# 1013-B-solarwhat-power.net
KiCad netlist of a schematic drawn in EAGLE
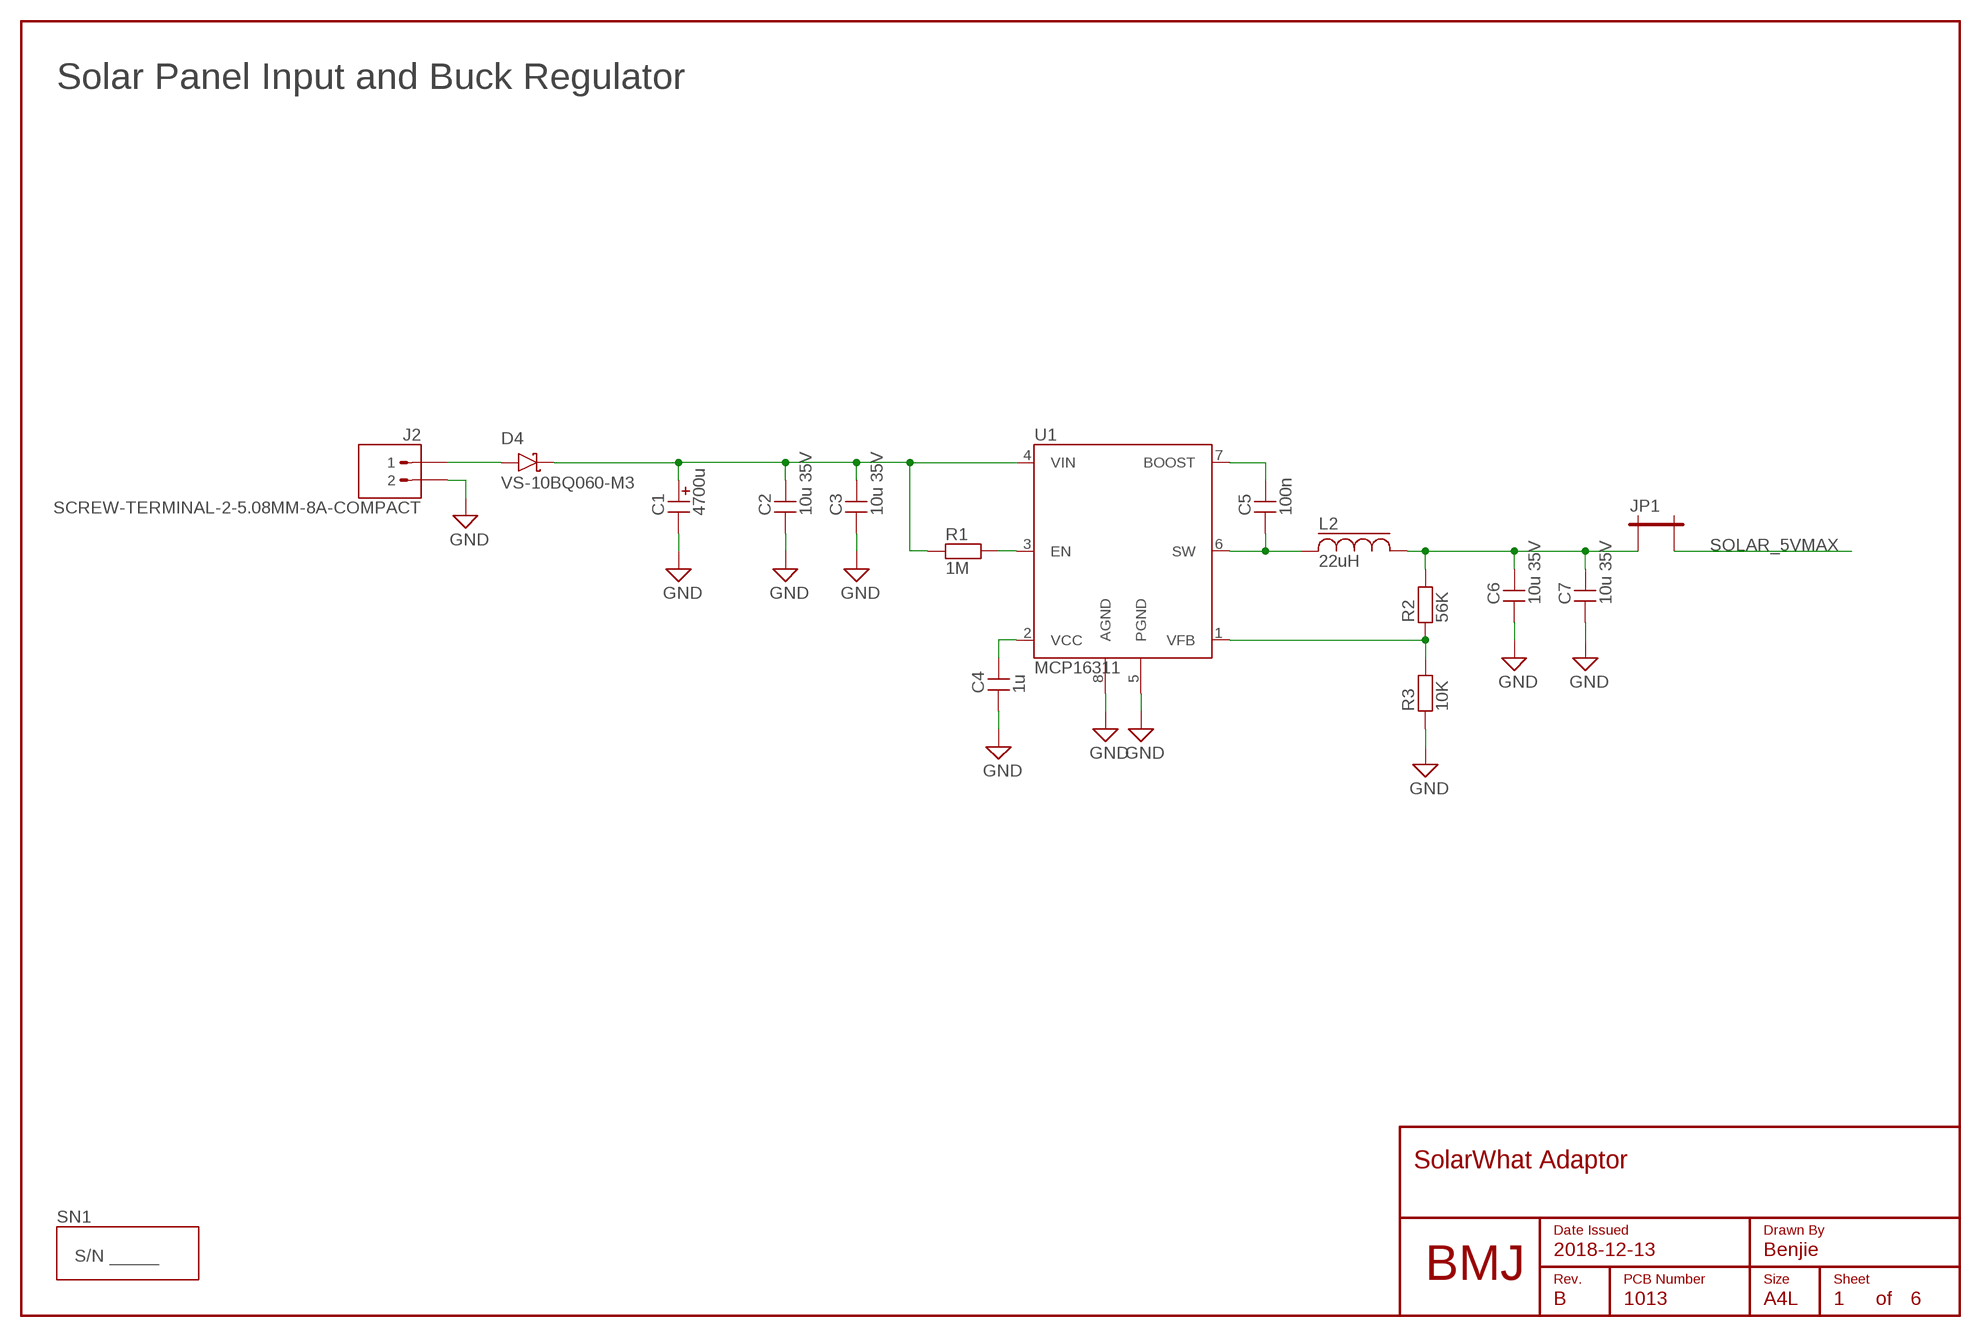
[diagram p0: schematic, sheet 1]
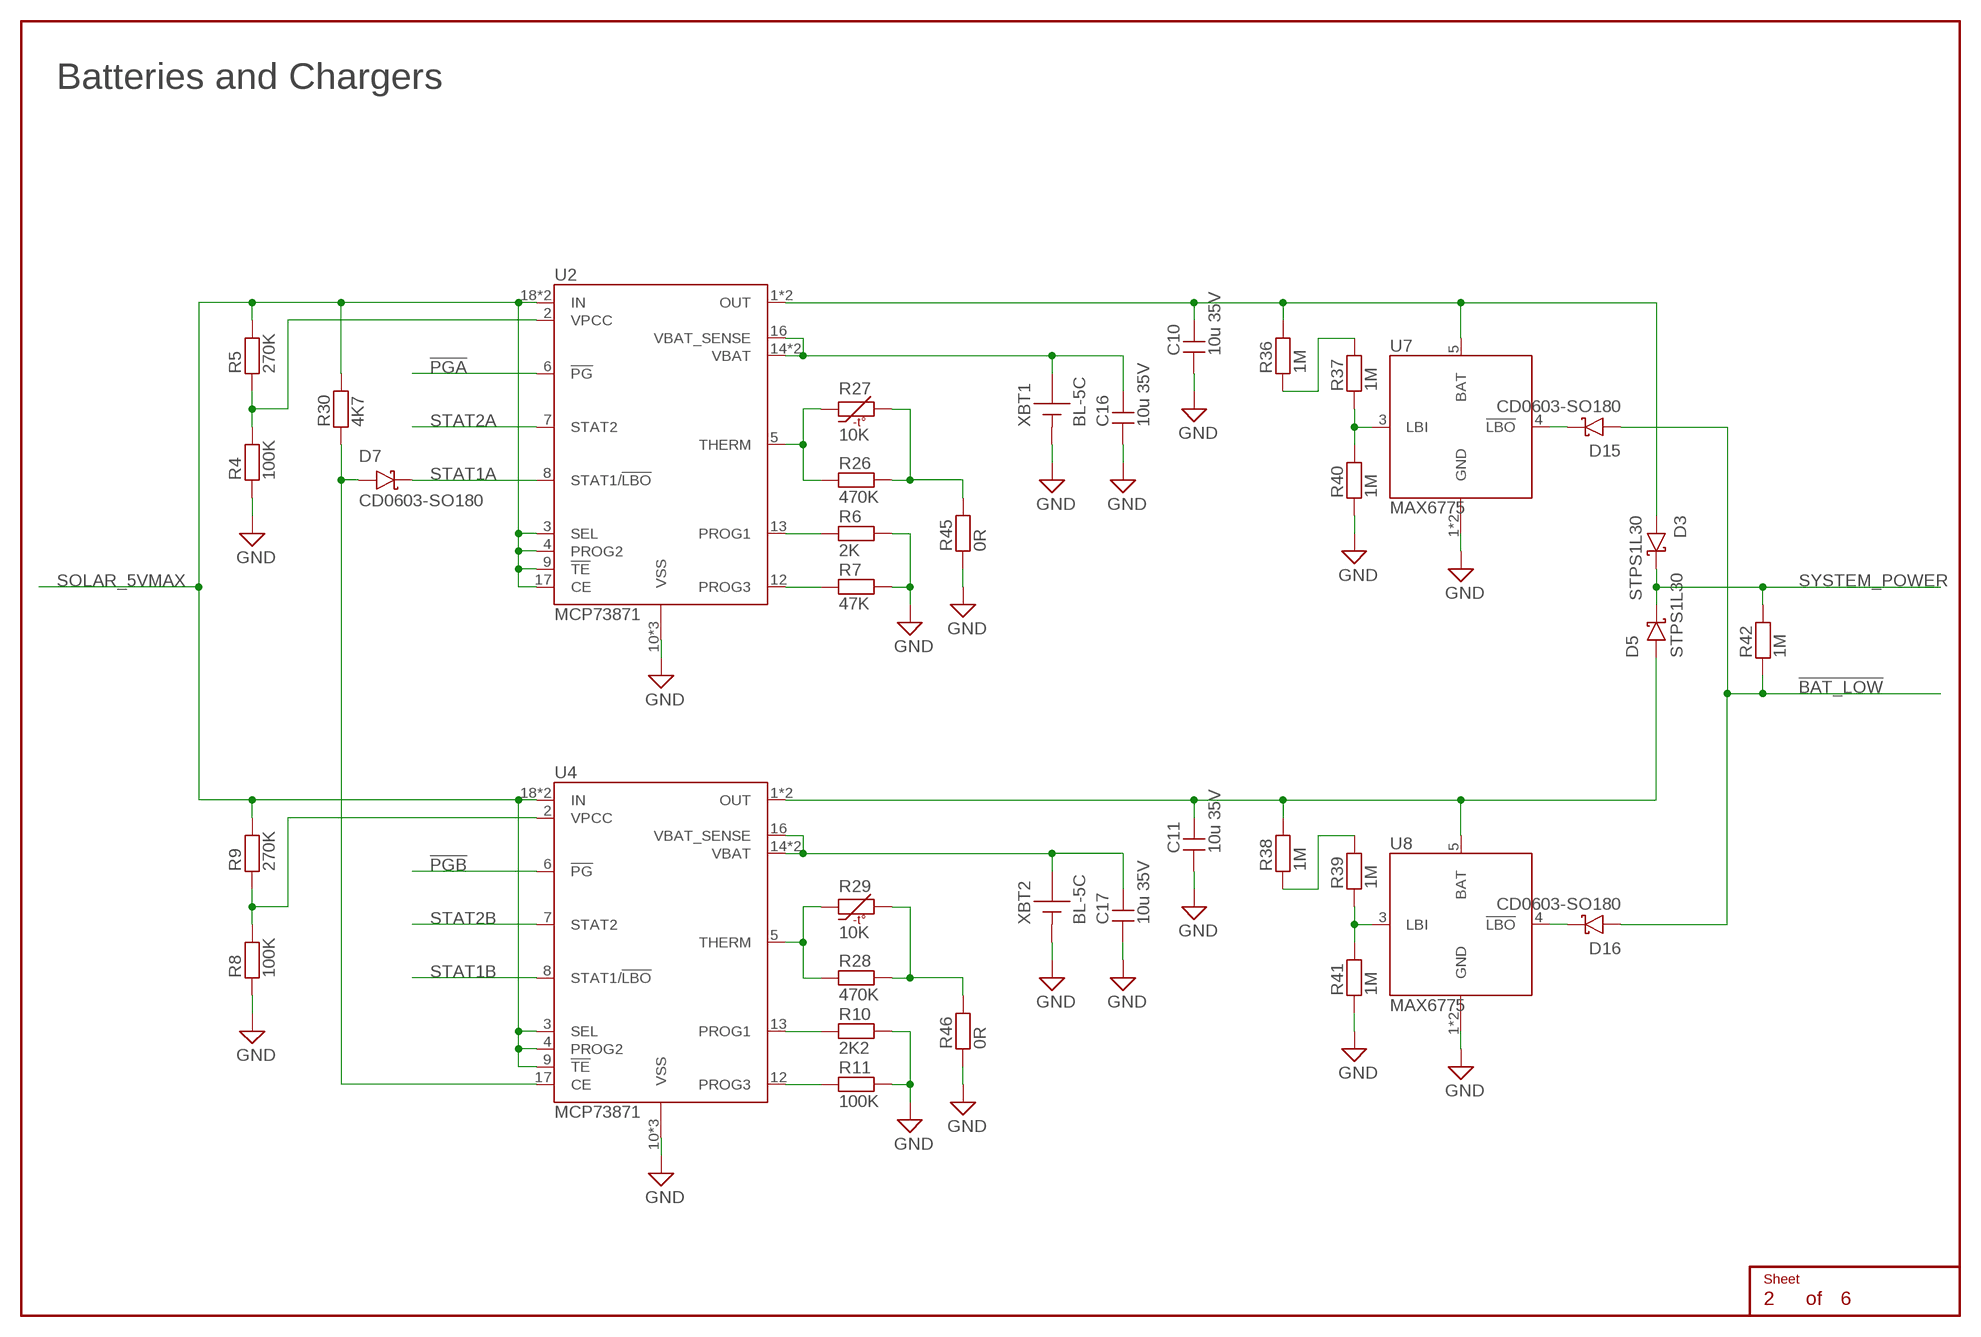
[diagram p1: schematic, sheet 2]
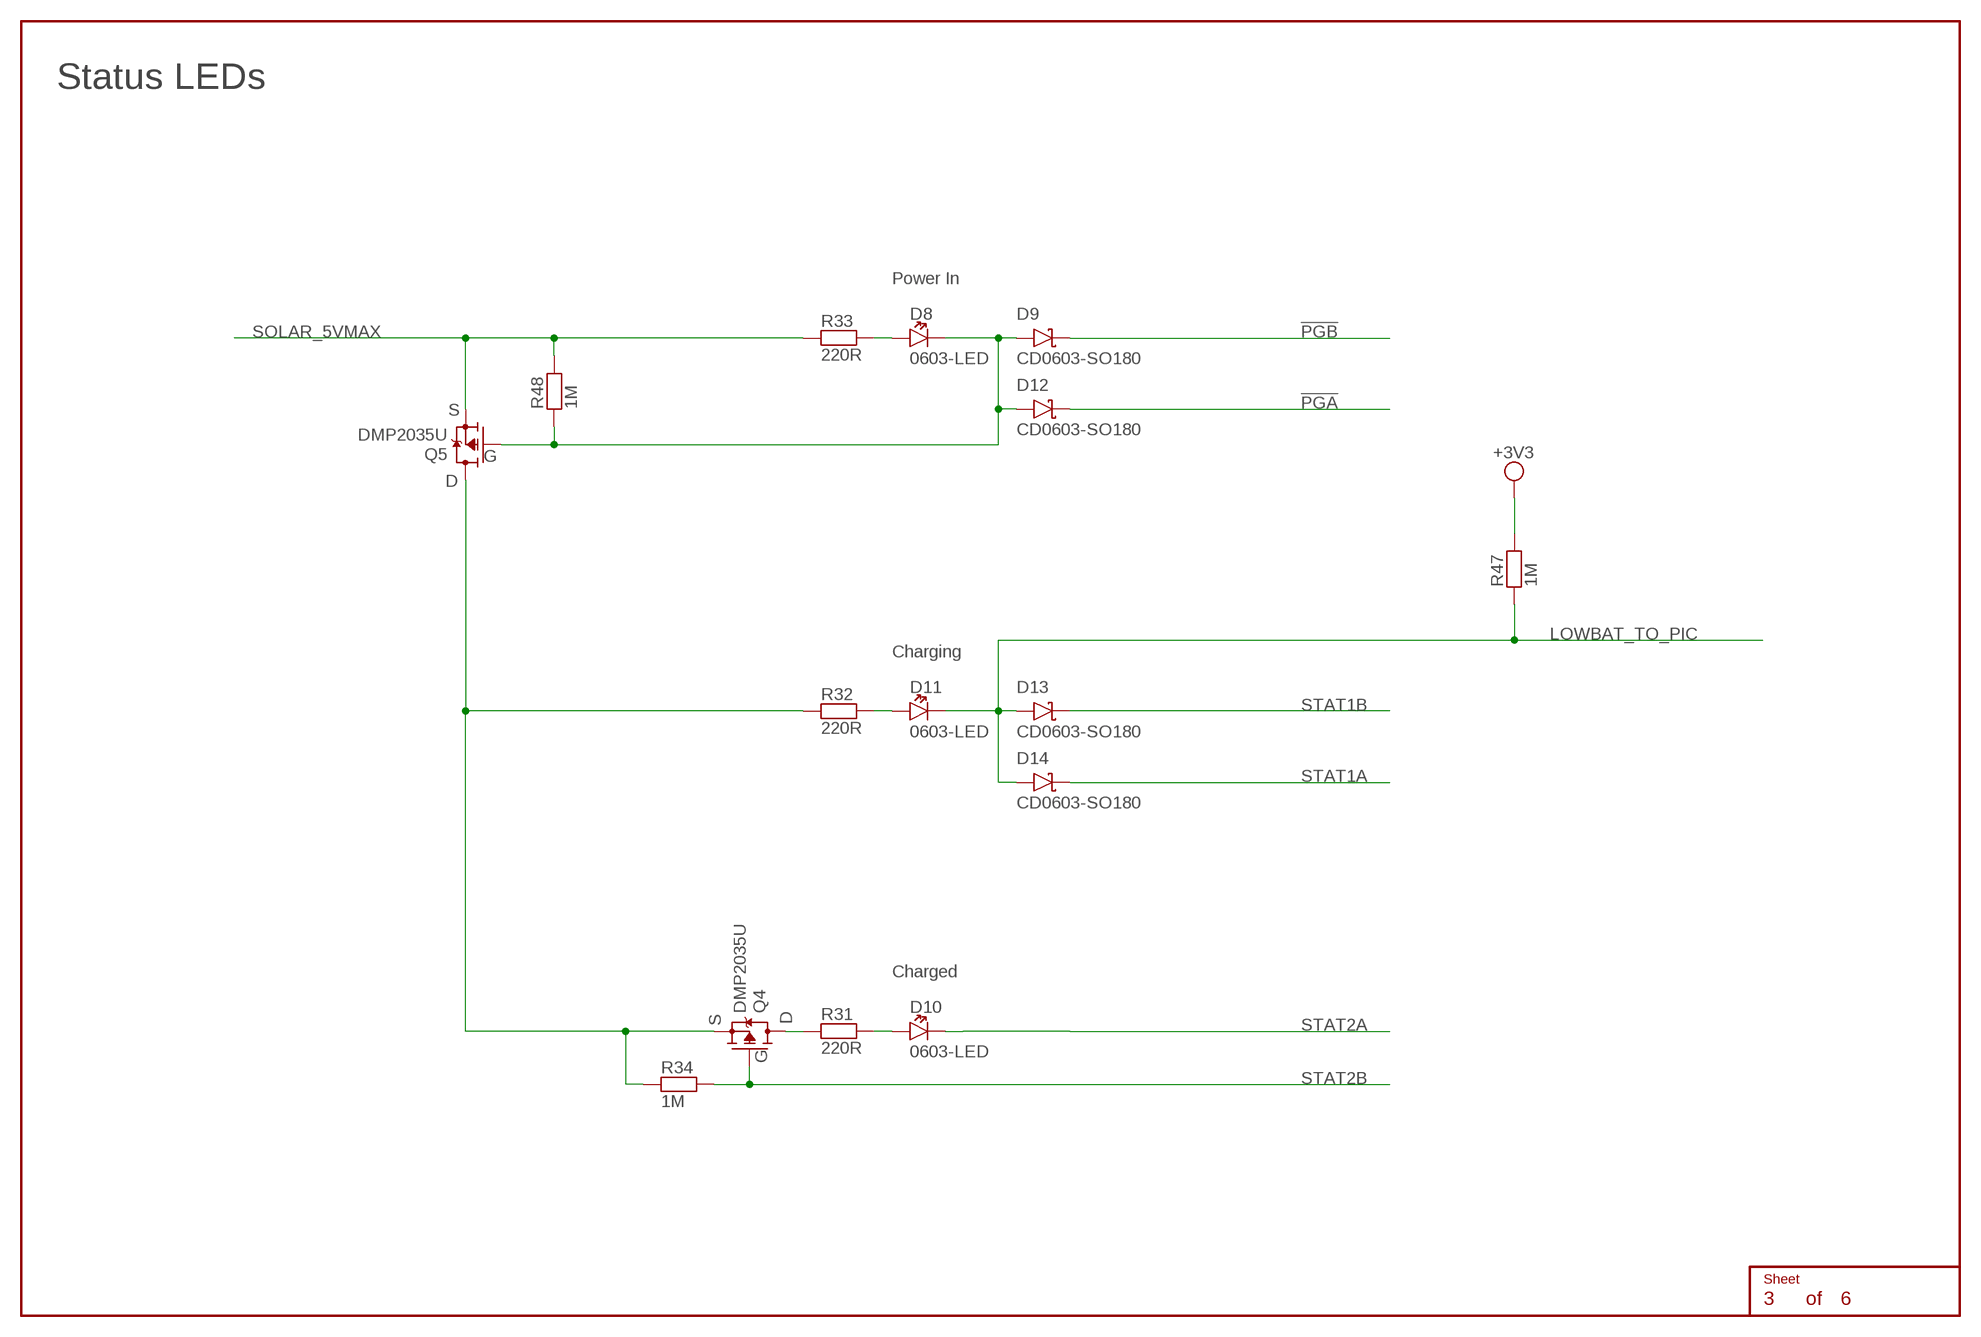
[diagram p2: schematic, sheet 3]
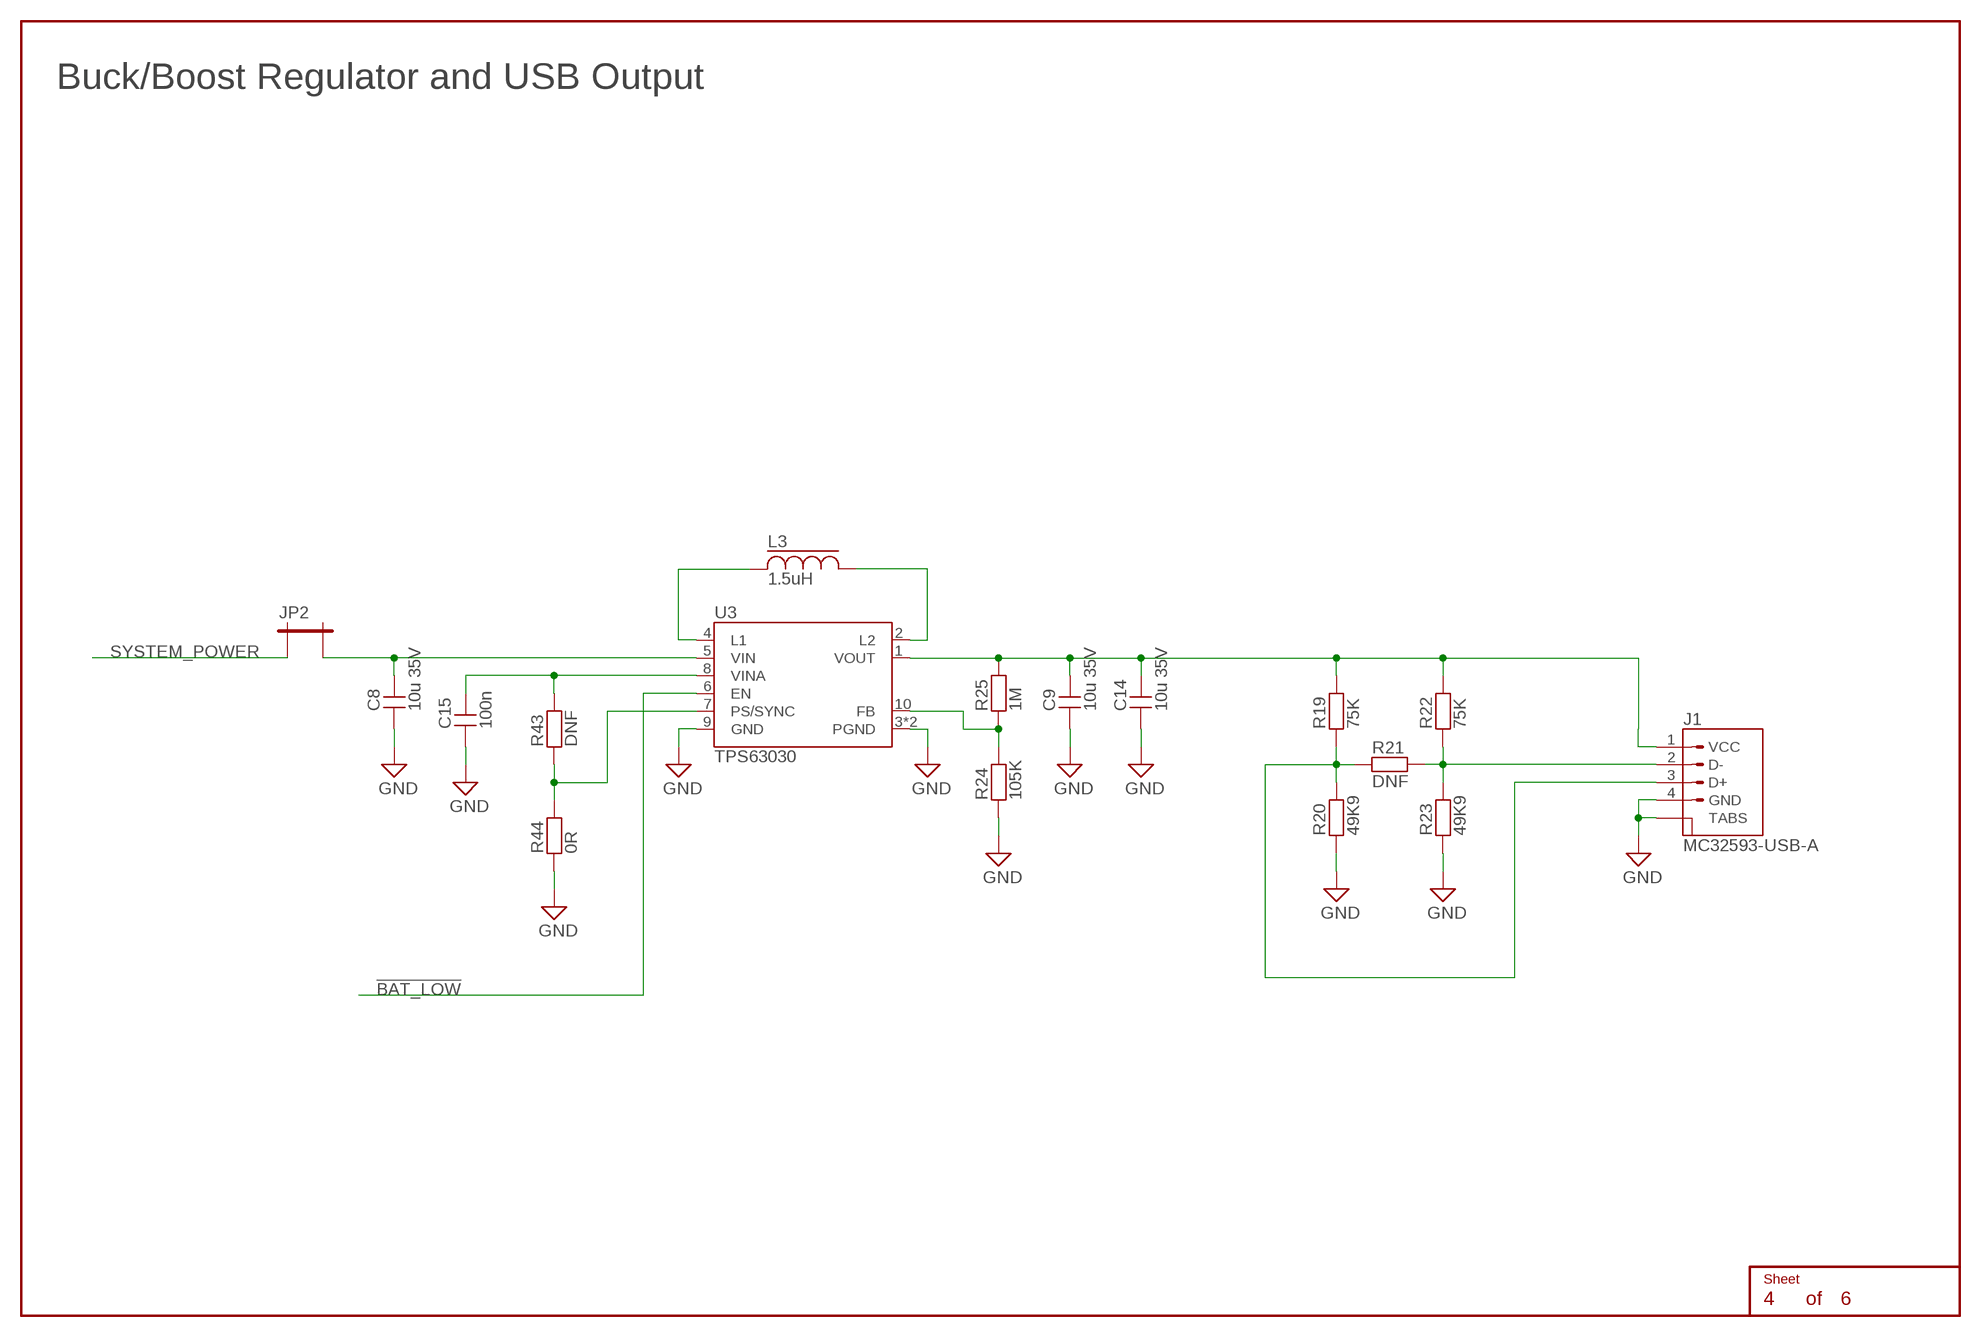
[diagram p3: schematic, sheet 4]
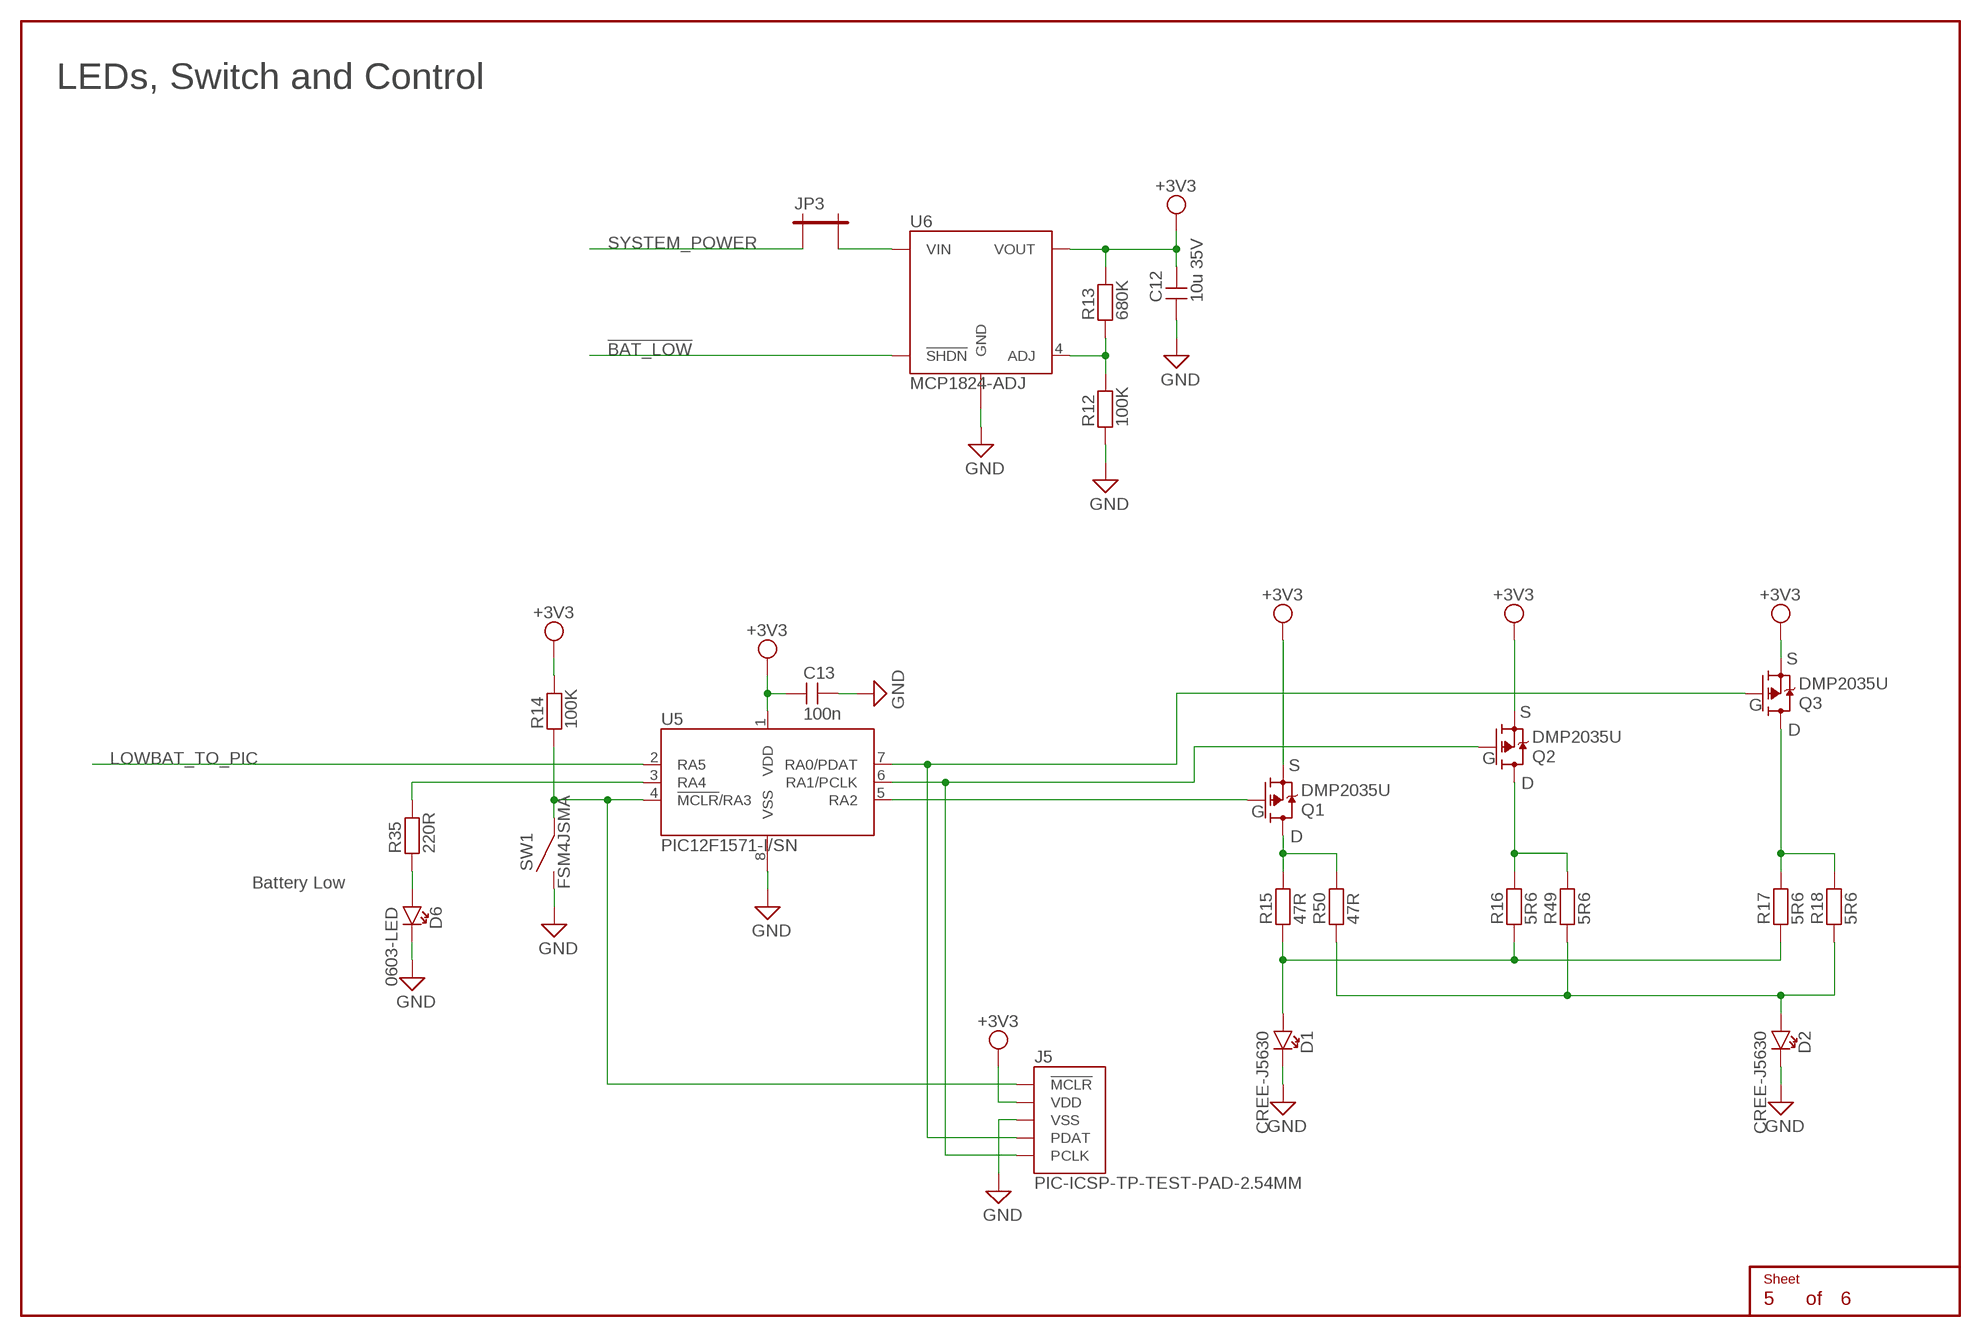
[diagram p4: schematic, sheet 5]
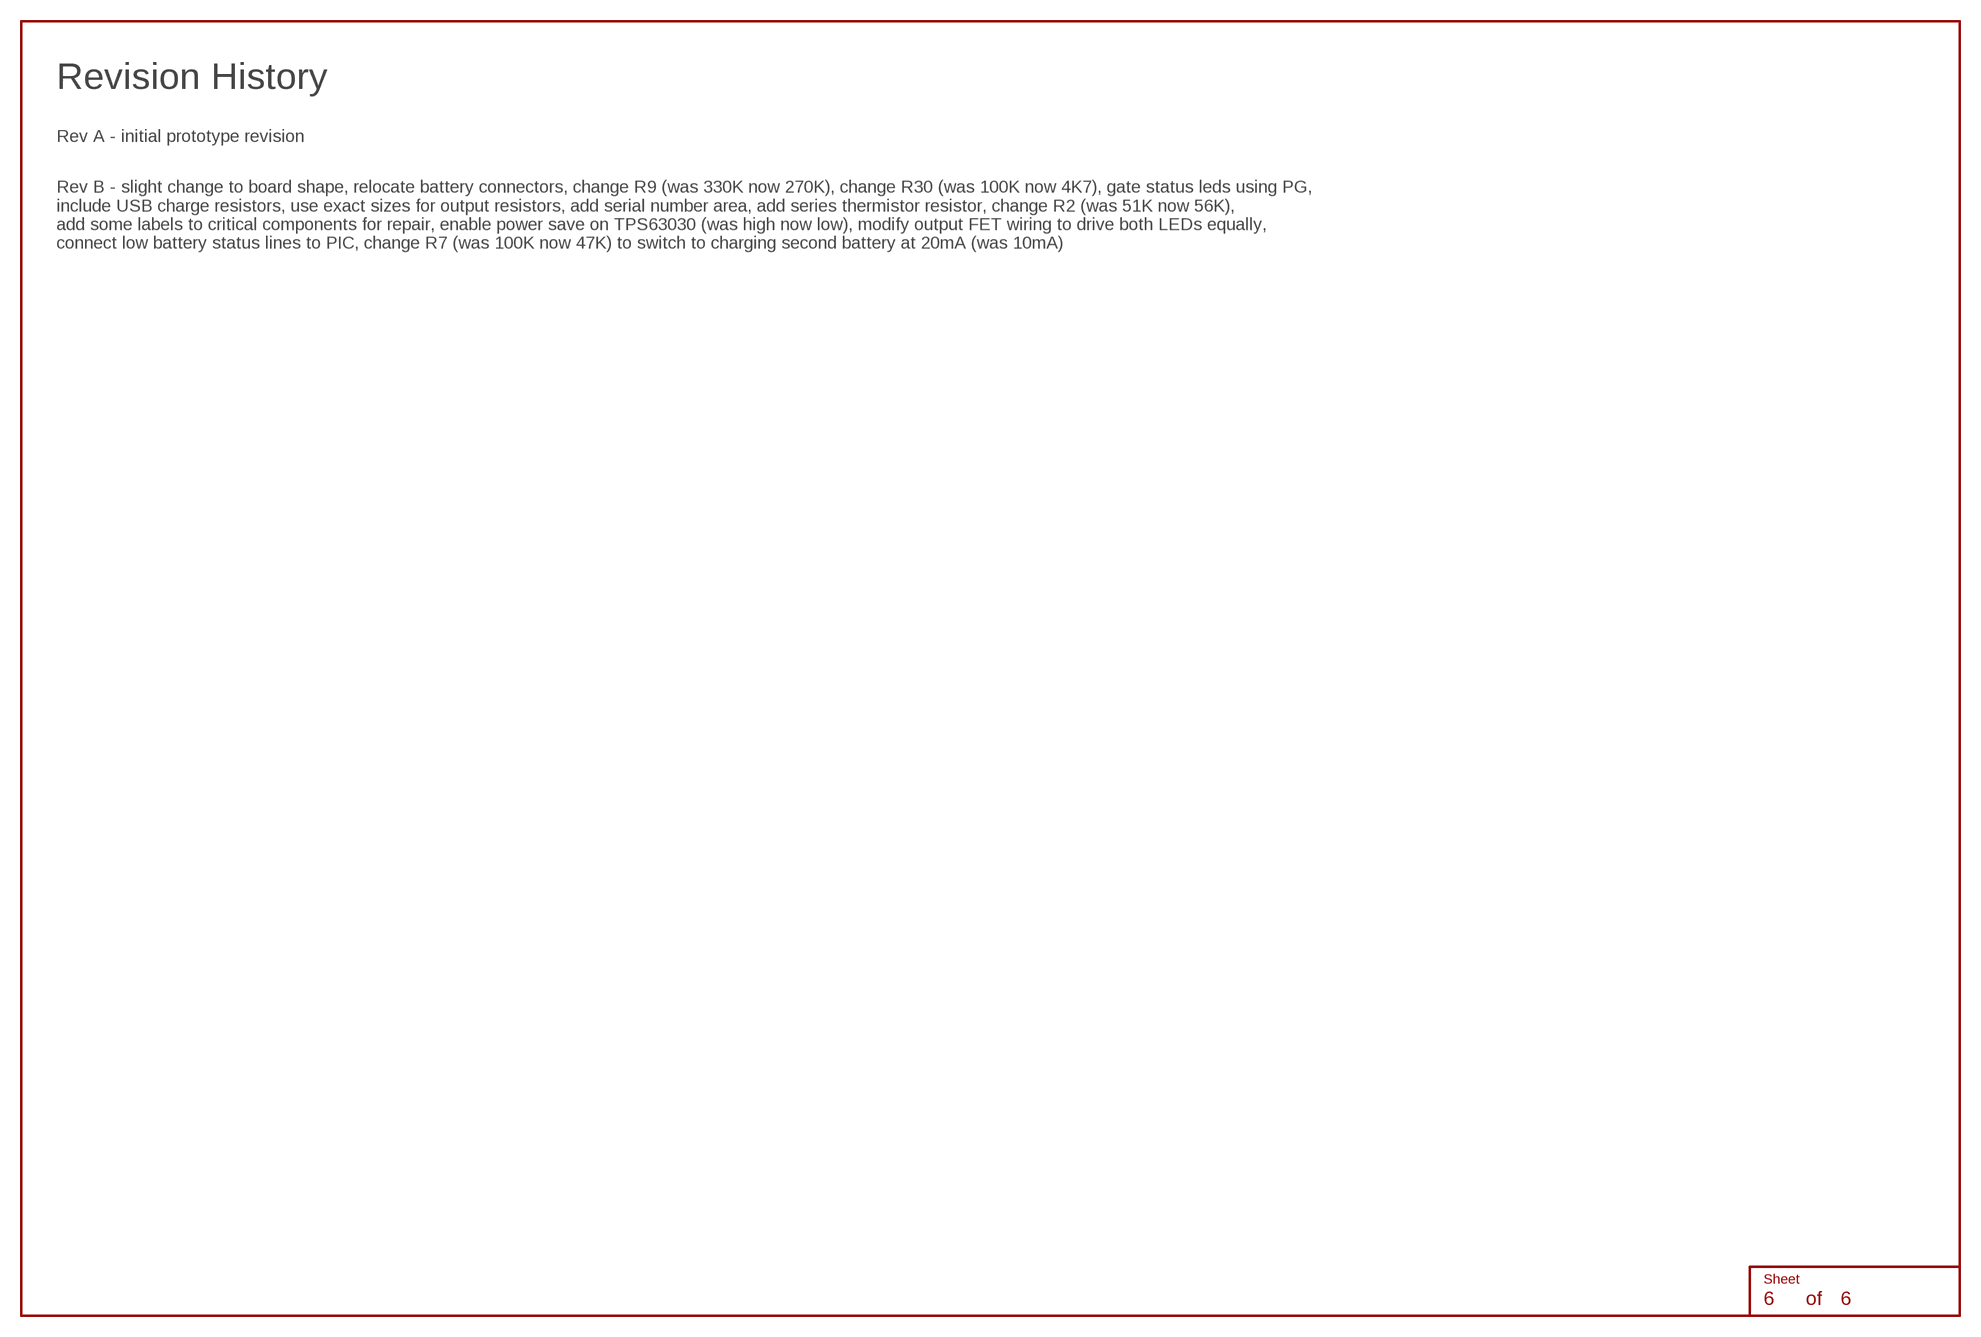
[diagram p5: schematic, sheet 6]

(export (version "E")
  (design (tool "Eeschema 10.0.6"))
  (components
    (comp (ref "C12")
      (value "10u 35V")
      (footprint "eagle-import:1206")
      (fields (field (name "MPN") "1206 10uF 35V 10% X7R"))
      (libsource (lib "eagle-import") (part "1206-10U-35V"))
    )
    (comp (ref "C13")
      (value "100n")
      (footprint "eagle-import:0603")
      (fields (field (name "MPN") "0603 100nF 50V 10% X7R"))
      (libsource (lib "eagle-import") (part "0603-100N"))
    )
    (comp (ref "D1")
      (value "CREE-J5630")
      (footprint "eagle-import:CREE-J5630")
      (libsource (lib "eagle-import") (part "CREE-J5630"))
    )
    (comp (ref "D2")
      (value "CREE-J5630")
      (footprint "eagle-import:CREE-J5630")
      (libsource (lib "eagle-import") (part "CREE-J5630"))
    )
    (comp (ref "D6")
      (value "0603-LED")
      (footprint "eagle-import:0603-LED")
      (fields (field (name "MPN") "TruOpto OSR50603C1E"))
      (libsource (lib "eagle-import") (part "0603-LED"))
    )
    (comp (ref "FRAME4")
      (value "A4L-CONTINUATION")
      (footprint "eagle-import:EMPTY")
      (libsource (lib "eagle-import") (part "A4L-CONTINUATION"))
    )
    (comp (ref "J5")
      (value "PIC-ICSP-TP-TEST-PAD-2.54MM")
      (footprint "eagle-import:PIC-ICSP-TEST-PAD-2.54MM")
      (libsource (lib "eagle-import") (part "PIC-ICSP-TP-TEST-PAD-2.54MM"))
    )
    (comp (ref "JP3")
      (value "SOLDER-JUMPER-2MM")
      (footprint "eagle-import:SOLDER-JUMPER-2MM")
      (libsource (lib "eagle-import") (part "SOLDER-JUMPER-2MM"))
    )
    (comp (ref "Q1")
      (value "DMP2035U")
      (footprint "eagle-import:SOT-23")
      (fields (field (name "MPN") "Diodes Inc DMP2035U"))
      (libsource (lib "eagle-import") (part "DMP2035U"))
    )
    (comp (ref "Q2")
      (value "DMP2035U")
      (footprint "eagle-import:SOT-23")
      (fields (field (name "MPN") "Diodes Inc DMP2035U"))
      (libsource (lib "eagle-import") (part "DMP2035U"))
    )
    (comp (ref "Q3")
      (value "DMP2035U")
      (footprint "eagle-import:SOT-23")
      (fields (field (name "MPN") "Diodes Inc DMP2035U"))
      (libsource (lib "eagle-import") (part "DMP2035U"))
    )
    (comp (ref "R12")
      (value "100K")
      (footprint "eagle-import:0603")
      (fields (field (name "MPN") "0603 100K 1% 100mW"))
      (libsource (lib "eagle-import") (part "0603-1%-100K"))
    )
    (comp (ref "R13")
      (value "680K")
      (footprint "eagle-import:0603")
      (fields (field (name "MPN") "0603 680K 1% 100mW"))
      (libsource (lib "eagle-import") (part "0603-1%-680K"))
    )
    (comp (ref "R14")
      (value "100K")
      (footprint "eagle-import:0603")
      (fields (field (name "MPN") "0603 100K 1% 100mW"))
      (libsource (lib "eagle-import") (part "0603-1%-100K"))
    )
    (comp (ref "R15")
      (value "47R")
      (footprint "eagle-import:0603")
      (fields (field (name "MPN") "0603 47R 1% 100mW"))
      (libsource (lib "eagle-import") (part "0603-1%-47R"))
    )
    (comp (ref "R16")
      (value "5R6")
      (footprint "eagle-import:0805")
      (libsource (lib "eagle-import") (part "0805"))
    )
    (comp (ref "R17")
      (value "5R6")
      (footprint "eagle-import:0805")
      (libsource (lib "eagle-import") (part "0805"))
    )
    (comp (ref "R18")
      (value "5R6")
      (footprint "eagle-import:0805")
      (libsource (lib "eagle-import") (part "0805"))
    )
    (comp (ref "R35")
      (value "220R")
      (footprint "eagle-import:0603")
      (fields (field (name "MPN") "0603 220R 1% 100mW"))
      (libsource (lib "eagle-import") (part "0603-1%-220R"))
    )
    (comp (ref "R49")
      (value "5R6")
      (footprint "eagle-import:0805")
      (libsource (lib "eagle-import") (part "0805"))
    )
    (comp (ref "R50")
      (value "47R")
      (footprint "eagle-import:0603")
      (fields (field (name "MPN") "0603 47R 1% 100mW"))
      (libsource (lib "eagle-import") (part "0603-1%-47R"))
    )
    (comp (ref "SW1")
      (value "FSM4JSMA")
      (footprint "eagle-import:ALCOSWITCH-FSM4JSMA")
      (fields (field (name "MPN") "Alcoswitch FSM4JSMA"))
      (libsource (lib "eagle-import") (part "FSM4JSMA"))
    )
    (comp (ref "U5")
      (value "PIC12F1571-I/SN")
      (footprint "eagle-import:SOIC-8")
      (fields (field (name "MPN") "Microchip PIC12F1571-I/SN"))
      (libsource (lib "eagle-import") (part "PIC12F1571-I/SN"))
    )
    (comp (ref "U6")
      (value "MCP1824-ADJ")
      (footprint "eagle-import:SOT-23-5")
      (libsource (lib "eagle-import") (part "MCP1824-ADJ"))
    )
    (comp (ref "C1")
      (value "4700u")
      (footprint "eagle-import:18X36-TH-FLAT")
      (fields (field (name "MPN") "Panasonic ECA1VAM472X"))
      (libsource (lib "eagle-import") (part "BIG-ELECTROLYTIC"))
    )
    (comp (ref "C2")
      (value "10u 35V")
      (footprint "eagle-import:1206")
      (fields (field (name "MPN") "1206 10uF 35V 10% X7R"))
      (libsource (lib "eagle-import") (part "1206-10U-35V"))
    )
    (comp (ref "C3")
      (value "10u 35V")
      (footprint "eagle-import:1206")
      (fields (field (name "MPN") "1206 10uF 35V 10% X7R"))
      (libsource (lib "eagle-import") (part "1206-10U-35V"))
    )
    (comp (ref "C4")
      (value "1u")
      (footprint "eagle-import:0805")
      (fields (field (name "MPN") "0805 1uF 50V 10% X7R"))
      (libsource (lib "eagle-import") (part "0805-1U"))
    )
    (comp (ref "C5")
      (value "100n")
      (footprint "eagle-import:0603")
      (fields (field (name "MPN") "0603 100nF 50V 10% X7R"))
      (libsource (lib "eagle-import") (part "0603-100N"))
    )
    (comp (ref "C6")
      (value "10u 35V")
      (footprint "eagle-import:1206")
      (fields (field (name "MPN") "1206 10uF 35V 10% X7R"))
      (libsource (lib "eagle-import") (part "1206-10U-35V"))
    )
    (comp (ref "C7")
      (value "10u 35V")
      (footprint "eagle-import:1206")
      (fields (field (name "MPN") "1206 10uF 35V 10% X7R"))
      (libsource (lib "eagle-import") (part "1206-10U-35V"))
    )
    (comp (ref "D4")
      (value "VS-10BQ060-M3")
      (footprint "eagle-import:SMB-ST")
      (fields (field (name "MPN") "Vishay VS-10BQ060-M3"))
      (libsource (lib "eagle-import") (part "VS-10BQ060-M3"))
    )
    (comp (ref "FRAME1")
      (value "A4L-NEW")
      (footprint "eagle-import:PCB-ID")
      (fields
        (field (name "DATEISSUED") "2018-12-13")
        (field (name "PCBNUMBER") "1013")
        (field (name "REVISION") "B")
        (field (name "TITLE") "SolarWhat Adaptor")
        (field (name "DRAWNBY") "Benjie")
      )
      (libsource (lib "eagle-import") (part "A4L-NEW"))
    )
    (comp (ref "J2")
      (value "SCREW-TERMINAL-2-5.08MM-8A-COMPACT")
      (footprint "eagle-import:CTBP0508_2")
      (fields (field (name "MPN") "CamdenBoss CTBP0508/2"))
      (libsource (lib "eagle-import") (part "SCREW-TERMINAL-2-5.08MM-8A-COMPACT"))
    )
    (comp (ref "JP1")
      (value "SOLDER-JUMPER-2MM")
      (footprint "eagle-import:SOLDER-JUMPER-2MM")
      (libsource (lib "eagle-import") (part "SOLDER-JUMPER-2MM"))
    )
    (comp (ref "L2")
      (value "22uH")
      (footprint "eagle-import:TDK-VLSX6045EX")
      (fields (field (name "MPN") "VLS6045EX-220M"))
      (libsource (lib "eagle-import") (part "TDK-VLSX6045EX-220M"))
    )
    (comp (ref "LOGO1")
      (value "BMJ-LOGO")
      (footprint "eagle-import:BMJ-LOGO")
      (libsource (lib "eagle-import") (part "BMJ-LOGO"))
    )
    (comp (ref "R1")
      (value "1M")
      (footprint "eagle-import:0603")
      (fields (field (name "MPN") "0603 1M 1% 100mW"))
      (libsource (lib "eagle-import") (part "0603-1%-1M"))
    )
    (comp (ref "R2")
      (value "56K")
      (footprint "eagle-import:0603")
      (libsource (lib "eagle-import") (part "0603-1%-56K"))
    )
    (comp (ref "R3")
      (value "10K")
      (footprint "eagle-import:0603")
      (fields (field (name "MPN") "0603 10K 1% 100mW"))
      (libsource (lib "eagle-import") (part "0603-1%-10K"))
    )
    (comp (ref "SN1")
      (value "SERIAL-NUMBER-AREA")
      (footprint "eagle-import:SERIAL-NUMBER-AREA-SMALL")
      (libsource (lib "eagle-import") (part "SERIAL-NUMBER-AREA"))
    )
    (comp (ref "U1")
      (value "MCP16311")
      (footprint "eagle-import:MSOP-8")
      (fields (field (name "MPN") "Microchip MCP16311T-E/MS"))
      (libsource (lib "eagle-import") (part "MCP16311"))
    )
    (comp (ref "C8")
      (value "10u 35V")
      (footprint "eagle-import:1206")
      (fields (field (name "MPN") "1206 10uF 35V 10% X7R"))
      (libsource (lib "eagle-import") (part "1206-10U-35V"))
    )
    (comp (ref "C9")
      (value "10u 35V")
      (footprint "eagle-import:1206")
      (fields (field (name "MPN") "1206 10uF 35V 10% X7R"))
      (libsource (lib "eagle-import") (part "1206-10U-35V"))
    )
    (comp (ref "C14")
      (value "10u 35V")
      (footprint "eagle-import:1206")
      (fields (field (name "MPN") "1206 10uF 35V 10% X7R"))
      (libsource (lib "eagle-import") (part "1206-10U-35V"))
    )
    (comp (ref "C15")
      (value "100n")
      (footprint "eagle-import:0603")
      (fields (field (name "MPN") "0603 100nF 50V 10% X7R"))
      (libsource (lib "eagle-import") (part "0603-100N"))
    )
    (comp (ref "FRAME3")
      (value "A4L-CONTINUATION")
      (footprint "eagle-import:EMPTY")
      (libsource (lib "eagle-import") (part "A4L-CONTINUATION"))
    )
    (comp (ref "J1")
      (value "MC32593-USB-A")
      (footprint "eagle-import:MC32593")
      (fields (field (name "MPN") "Multicomp MC32593"))
      (libsource (lib "eagle-import") (part "MC32593-USB-A"))
    )
    (comp (ref "JP2")
      (value "SOLDER-JUMPER-2MM")
      (footprint "eagle-import:SOLDER-JUMPER-2MM")
      (libsource (lib "eagle-import") (part "SOLDER-JUMPER-2MM"))
    )
    (comp (ref "L3")
      (value "1.5uH")
      (footprint "eagle-import:TDK-VLSX5045EX")
      (fields (field (name "MPN") "TDK VLS5045EX-1R5N"))
      (libsource (lib "eagle-import") (part "TDK-VLSX5045EX-1R5N"))
    )
    (comp (ref "R19")
      (value "75K")
      (footprint "eagle-import:0603")
      (libsource (lib "eagle-import") (part "0603-1%-75K"))
    )
    (comp (ref "R20")
      (value "49K9")
      (footprint "eagle-import:0603")
      (libsource (lib "eagle-import") (part "0603-1%-49K9"))
    )
    (comp (ref "R21")
      (value "DNF")
      (footprint "eagle-import:0603")
      (libsource (lib "eagle-import") (part "CHIP-0603-DNF"))
    )
    (comp (ref "R22")
      (value "75K")
      (footprint "eagle-import:0603")
      (libsource (lib "eagle-import") (part "0603-1%-75K"))
    )
    (comp (ref "R23")
      (value "49K9")
      (footprint "eagle-import:0603")
      (libsource (lib "eagle-import") (part "0603-1%-49K9"))
    )
    (comp (ref "R24")
      (value "105K")
      (footprint "eagle-import:0603")
      (libsource (lib "eagle-import") (part "0603-1%-105K"))
    )
    (comp (ref "R25")
      (value "1M")
      (footprint "eagle-import:0603")
      (fields (field (name "MPN") "0603 1M 1% 100mW"))
      (libsource (lib "eagle-import") (part "0603-1%-1M"))
    )
    (comp (ref "R43")
      (value "DNF")
      (footprint "eagle-import:0603")
      (libsource (lib "eagle-import") (part "CHIP-0603-DNF"))
    )
    (comp (ref "R44")
      (value "0R")
      (footprint "eagle-import:0603")
      (fields (field (name "MPN") "0603 0R 1% 100mW"))
      (libsource (lib "eagle-import") (part "0603-1%-0R"))
    )
    (comp (ref "U3")
      (value "TPS63030")
      (footprint "eagle-import:VSON-10")
      (fields (field (name "MPN") "TI TPS63030"))
      (libsource (lib "eagle-import") (part "TPS63030"))
    )
    (comp (ref "D8")
      (value "0603-LED")
      (footprint "eagle-import:0603-LED")
      (fields (field (name "MPN") "TruOpto OSR50603C1E"))
      (libsource (lib "eagle-import") (part "0603-LED"))
    )
    (comp (ref "D9")
      (value "CD0603-SO180")
      (footprint "eagle-import:0603")
      (fields (field (name "MPN") "Bourns CD0603-S0180"))
      (libsource (lib "eagle-import") (part "CD0603-SO180"))
    )
    (comp (ref "D10")
      (value "0603-LED")
      (footprint "eagle-import:0603-LED")
      (fields (field (name "MPN") "TruOpto OSR50603C1E"))
      (libsource (lib "eagle-import") (part "0603-LED"))
    )
    (comp (ref "D11")
      (value "0603-LED")
      (footprint "eagle-import:0603-LED")
      (fields (field (name "MPN") "TruOpto OSR50603C1E"))
      (libsource (lib "eagle-import") (part "0603-LED"))
    )
    (comp (ref "D12")
      (value "CD0603-SO180")
      (footprint "eagle-import:0603")
      (fields (field (name "MPN") "Bourns CD0603-S0180"))
      (libsource (lib "eagle-import") (part "CD0603-SO180"))
    )
    (comp (ref "D13")
      (value "CD0603-SO180")
      (footprint "eagle-import:0603")
      (fields (field (name "MPN") "Bourns CD0603-S0180"))
      (libsource (lib "eagle-import") (part "CD0603-SO180"))
    )
    (comp (ref "D14")
      (value "CD0603-SO180")
      (footprint "eagle-import:0603")
      (fields (field (name "MPN") "Bourns CD0603-S0180"))
      (libsource (lib "eagle-import") (part "CD0603-SO180"))
    )
    (comp (ref "FRAME5")
      (value "A4L-CONTINUATION")
      (footprint "eagle-import:EMPTY")
      (libsource (lib "eagle-import") (part "A4L-CONTINUATION"))
    )
    (comp (ref "Q4")
      (value "DMP2035U")
      (footprint "eagle-import:SOT-23")
      (fields (field (name "MPN") "Diodes Inc DMP2035U"))
      (libsource (lib "eagle-import") (part "DMP2035U"))
    )
    (comp (ref "Q5")
      (value "DMP2035U")
      (footprint "eagle-import:SOT-23")
      (fields (field (name "MPN") "Diodes Inc DMP2035U"))
      (libsource (lib "eagle-import") (part "DMP2035U"))
    )
    (comp (ref "R31")
      (value "220R")
      (footprint "eagle-import:0603")
      (fields (field (name "MPN") "0603 220R 1% 100mW"))
      (libsource (lib "eagle-import") (part "0603-1%-220R"))
    )
    (comp (ref "R32")
      (value "220R")
      (footprint "eagle-import:0603")
      (fields (field (name "MPN") "0603 220R 1% 100mW"))
      (libsource (lib "eagle-import") (part "0603-1%-220R"))
    )
    (comp (ref "R33")
      (value "220R")
      (footprint "eagle-import:0603")
      (fields (field (name "MPN") "0603 220R 1% 100mW"))
      (libsource (lib "eagle-import") (part "0603-1%-220R"))
    )
    (comp (ref "R34")
      (value "1M")
      (footprint "eagle-import:0603")
      (fields (field (name "MPN") "0603 1M 1% 100mW"))
      (libsource (lib "eagle-import") (part "0603-1%-1M"))
    )
    (comp (ref "R47")
      (value "1M")
      (footprint "eagle-import:0603")
      (fields (field (name "MPN") "0603 1M 1% 100mW"))
      (libsource (lib "eagle-import") (part "0603-1%-1M"))
    )
    (comp (ref "R48")
      (value "1M")
      (footprint "eagle-import:0603")
      (fields (field (name "MPN") "0603 1M 1% 100mW"))
      (libsource (lib "eagle-import") (part "0603-1%-1M"))
    )
    (comp (ref "C10")
      (value "10u 35V")
      (footprint "eagle-import:1206")
      (fields (field (name "MPN") "1206 10uF 35V 10% X7R"))
      (libsource (lib "eagle-import") (part "1206-10U-35V"))
    )
    (comp (ref "C11")
      (value "10u 35V")
      (footprint "eagle-import:1206")
      (fields (field (name "MPN") "1206 10uF 35V 10% X7R"))
      (libsource (lib "eagle-import") (part "1206-10U-35V"))
    )
    (comp (ref "C16")
      (value "10u 35V")
      (footprint "eagle-import:1206")
      (fields (field (name "MPN") "1206 10uF 35V 10% X7R"))
      (libsource (lib "eagle-import") (part "1206-10U-35V"))
    )
    (comp (ref "C17")
      (value "10u 35V")
      (footprint "eagle-import:1206")
      (fields (field (name "MPN") "1206 10uF 35V 10% X7R"))
      (libsource (lib "eagle-import") (part "1206-10U-35V"))
    )
    (comp (ref "D3")
      (value "STPS1L30")
      (footprint "eagle-import:SMB-ST")
      (fields (field (name "MPN") "ST STPS1L30U"))
      (libsource (lib "eagle-import") (part "STPS1L30"))
    )
    (comp (ref "D5")
      (value "STPS1L30")
      (footprint "eagle-import:SMB-ST")
      (fields (field (name "MPN") "ST STPS1L30U"))
      (libsource (lib "eagle-import") (part "STPS1L30"))
    )
    (comp (ref "D7")
      (value "CD0603-SO180")
      (footprint "eagle-import:0603")
      (fields (field (name "MPN") "Bourns CD0603-S0180"))
      (libsource (lib "eagle-import") (part "CD0603-SO180"))
    )
    (comp (ref "D15")
      (value "CD0603-SO180")
      (footprint "eagle-import:0603")
      (fields (field (name "MPN") "Bourns CD0603-S0180"))
      (libsource (lib "eagle-import") (part "CD0603-SO180"))
    )
    (comp (ref "D16")
      (value "CD0603-SO180")
      (footprint "eagle-import:0603")
      (fields (field (name "MPN") "Bourns CD0603-S0180"))
      (libsource (lib "eagle-import") (part "CD0603-SO180"))
    )
    (comp (ref "FRAME2")
      (value "A4L-CONTINUATION")
      (footprint "eagle-import:EMPTY")
      (libsource (lib "eagle-import") (part "A4L-CONTINUATION"))
    )
    (comp (ref "R4")
      (value "100K")
      (footprint "eagle-import:0603")
      (fields (field (name "MPN") "0603 100K 1% 100mW"))
      (libsource (lib "eagle-import") (part "0603-1%-100K"))
    )
    (comp (ref "R5")
      (value "270K")
      (footprint "eagle-import:0603")
      (libsource (lib "eagle-import") (part "0603-1%-270K"))
    )
    (comp (ref "R6")
      (value "2K")
      (footprint "eagle-import:0603")
      (libsource (lib "eagle-import") (part "0603-1%-2K"))
    )
    (comp (ref "R7")
      (value "47K")
      (footprint "eagle-import:0603")
      (fields (field (name "MPN") "0603 47K 1% 100mW"))
      (libsource (lib "eagle-import") (part "0603-1%-47K"))
    )
    (comp (ref "R8")
      (value "100K")
      (footprint "eagle-import:0603")
      (fields (field (name "MPN") "0603 100K 1% 100mW"))
      (libsource (lib "eagle-import") (part "0603-1%-100K"))
    )
    (comp (ref "R9")
      (value "270K")
      (footprint "eagle-import:0603")
      (libsource (lib "eagle-import") (part "0603-1%-270K"))
    )
    (comp (ref "R10")
      (value "2K2")
      (footprint "eagle-import:0603")
      (fields (field (name "MPN") "0603 2.2K 1% 100mW"))
      (libsource (lib "eagle-import") (part "0603-1%-2K2"))
    )
    (comp (ref "R11")
      (value "100K")
      (footprint "eagle-import:0603")
      (fields (field (name "MPN") "0603 100K 1% 100mW"))
      (libsource (lib "eagle-import") (part "0603-1%-100K"))
    )
    (comp (ref "R26")
      (value "470K")
      (footprint "eagle-import:0603")
      (fields (field (name "MPN") "0603 470K 1% 100mW"))
      (libsource (lib "eagle-import") (part "0603-1%-470K"))
    )
    (comp (ref "R27")
      (value "10K")
      (footprint "eagle-import:0603")
      (libsource (lib "eagle-import") (part "NTC-0603-10K"))
    )
    (comp (ref "R28")
      (value "470K")
      (footprint "eagle-import:0603")
      (fields (field (name "MPN") "0603 470K 1% 100mW"))
      (libsource (lib "eagle-import") (part "0603-1%-470K"))
    )
    (comp (ref "R29")
      (value "10K")
      (footprint "eagle-import:0603")
      (libsource (lib "eagle-import") (part "NTC-0603-10K"))
    )
    (comp (ref "R30")
      (value "4K7")
      (footprint "eagle-import:0603")
      (fields (field (name "MPN") "0603 4.7K 1% 100mW"))
      (libsource (lib "eagle-import") (part "0603-1%-4K7"))
    )
    (comp (ref "R36")
      (value "1M")
      (footprint "eagle-import:0603")
      (fields (field (name "MPN") "0603 1M 1% 100mW"))
      (libsource (lib "eagle-import") (part "0603-1%-1M"))
    )
    (comp (ref "R37")
      (value "1M")
      (footprint "eagle-import:0603")
      (fields (field (name "MPN") "0603 1M 1% 100mW"))
      (libsource (lib "eagle-import") (part "0603-1%-1M"))
    )
    (comp (ref "R38")
      (value "1M")
      (footprint "eagle-import:0603")
      (fields (field (name "MPN") "0603 1M 1% 100mW"))
      (libsource (lib "eagle-import") (part "0603-1%-1M"))
    )
    (comp (ref "R39")
      (value "1M")
      (footprint "eagle-import:0603")
      (fields (field (name "MPN") "0603 1M 1% 100mW"))
      (libsource (lib "eagle-import") (part "0603-1%-1M"))
    )
    (comp (ref "R40")
      (value "1M")
      (footprint "eagle-import:0603")
      (fields (field (name "MPN") "0603 1M 1% 100mW"))
      (libsource (lib "eagle-import") (part "0603-1%-1M"))
    )
    (comp (ref "R41")
      (value "1M")
      (footprint "eagle-import:0603")
      (fields (field (name "MPN") "0603 1M 1% 100mW"))
      (libsource (lib "eagle-import") (part "0603-1%-1M"))
    )
    (comp (ref "R42")
      (value "1M")
      (footprint "eagle-import:0603")
      (fields (field (name "MPN") "0603 1M 1% 100mW"))
      (libsource (lib "eagle-import") (part "0603-1%-1M"))
    )
    (comp (ref "R45")
      (value "0R")
      (footprint "eagle-import:0603")
      (fields (field (name "MPN") "0603 0R 1% 100mW"))
      (libsource (lib "eagle-import") (part "0603-1%-0R"))
    )
    (comp (ref "R46")
      (value "0R")
      (footprint "eagle-import:0603")
      (fields (field (name "MPN") "0603 0R 1% 100mW"))
      (libsource (lib "eagle-import") (part "0603-1%-0R"))
    )
    (comp (ref "U2")
      (value "MCP73871")
      (footprint "eagle-import:QFN-20")
      (fields (field (name "MPN") "MCP73871-2CCI/ML"))
      (libsource (lib "eagle-import") (part "MCP73871"))
    )
    (comp (ref "U4")
      (value "MCP73871")
      (footprint "eagle-import:QFN-20")
      (fields (field (name "MPN") "MCP73871-2CCI/ML"))
      (libsource (lib "eagle-import") (part "MCP73871"))
    )
    (comp (ref "U7")
      (value "MAX6775")
      (footprint "eagle-import:SC70")
      (libsource (lib "eagle-import") (part "MAX6775"))
    )
    (comp (ref "U8")
      (value "MAX6775")
      (footprint "eagle-import:SC70")
      (libsource (lib "eagle-import") (part "MAX6775"))
    )
    (comp (ref "XBT1")
      (value "BL-5C")
      (footprint "eagle-import:3MM-BATTERY-3WAY")
      (libsource (lib "eagle-import") (part "BL-5CBL5C"))
    )
    (comp (ref "XBT2")
      (value "BL-5C")
      (footprint "eagle-import:3MM-BATTERY-3WAY")
      (libsource (lib "eagle-import") (part "BL-5CBL5C"))
    )
    (comp (ref "FRAME6")
      (value "A4L-CONTINUATION")
      (footprint "eagle-import:EMPTY")
      (libsource (lib "eagle-import") (part "A4L-CONTINUATION"))
    )
  )
  (nets
    (net (code "1") (name "+3V3") (class "Default")
      (node (ref "C12") (pin "2") (pinfunction "2_2") (pintype "passive"))
      (node (ref "C13") (pin "1") (pinfunction "1_1") (pintype "passive"))
      (node (ref "J5") (pin "V+") (pinfunction "VDD_V+") (pintype "power_in"))
      (node (ref "Q1") (pin "2") (pinfunction "S_2") (pintype "passive"))
      (node (ref "Q2") (pin "2") (pinfunction "S_2") (pintype "passive"))
      (node (ref "Q3") (pin "2") (pinfunction "S_2") (pintype "passive"))
      (node (ref "R13") (pin "2") (pinfunction "2_2") (pintype "passive"))
      (node (ref "R14") (pin "2") (pinfunction "2_2") (pintype "passive"))
      (node (ref "R47") (pin "2") (pinfunction "2_2") (pintype "passive"))
      (node (ref "U5") (pin "1") (pinfunction "VDD_1") (pintype "power_in"))
      (node (ref "U6") (pin "5") (pinfunction "VOUT_5") (pintype "bidirectional"))
    )
    (net (code "2") (name "GND") (class "Default")
      (node (ref "C1") (pin "-") (pinfunction "-_-") (pintype "passive"))
      (node (ref "C10") (pin "1") (pinfunction "1_1") (pintype "passive"))
      (node (ref "C11") (pin "1") (pinfunction "1_1") (pintype "passive"))
      (node (ref "C12") (pin "1") (pinfunction "1_1") (pintype "passive"))
      (node (ref "C13") (pin "2") (pinfunction "2_2") (pintype "passive"))
      (node (ref "C14") (pin "1") (pinfunction "1_1") (pintype "passive"))
      (node (ref "C15") (pin "1") (pinfunction "1_1") (pintype "passive"))
      (node (ref "C16") (pin "1") (pinfunction "1_1") (pintype "passive"))
      (node (ref "C17") (pin "1") (pinfunction "1_1") (pintype "passive"))
      (node (ref "C2") (pin "1") (pinfunction "1_1") (pintype "passive"))
      (node (ref "C3") (pin "1") (pinfunction "1_1") (pintype "passive"))
      (node (ref "C4") (pin "1") (pinfunction "1_1") (pintype "passive"))
      (node (ref "C6") (pin "1") (pinfunction "1_1") (pintype "passive"))
      (node (ref "C7") (pin "1") (pinfunction "1_1") (pintype "passive"))
      (node (ref "C8") (pin "1") (pinfunction "1_1") (pintype "passive"))
      (node (ref "C9") (pin "1") (pinfunction "1_1") (pintype "passive"))
      (node (ref "D1") (pin "K") (pinfunction "C_K") (pintype "passive"))
      (node (ref "D2") (pin "K") (pinfunction "C_K") (pintype "passive"))
      (node (ref "D6") (pin "C") (pinfunction "C_C") (pintype "passive"))
      (node (ref "J1") (pin "4") (pinfunction "GND_4") (pintype "passive"))
      (node (ref "J1") (pin "TAB1") (pinfunction "TABS_TAB1") (pintype "passive"))
      (node (ref "J1") (pin "TAB2") (pinfunction "TABS_TAB2") (pintype "passive"))
      (node (ref "J2") (pin "2") (pinfunction "2_2") (pintype "passive"))
      (node (ref "J5") (pin "GND") (pinfunction "VSS_GND") (pintype "power_in"))
      (node (ref "R10") (pin "2") (pinfunction "2_2") (pintype "passive"))
      (node (ref "R11") (pin "2") (pinfunction "2_2") (pintype "passive"))
      (node (ref "R12") (pin "1") (pinfunction "1_1") (pintype "passive"))
      (node (ref "R20") (pin "1") (pinfunction "1_1") (pintype "passive"))
      (node (ref "R23") (pin "1") (pinfunction "1_1") (pintype "passive"))
      (node (ref "R24") (pin "1") (pinfunction "1_1") (pintype "passive"))
      (node (ref "R3") (pin "1") (pinfunction "1_1") (pintype "passive"))
      (node (ref "R4") (pin "1") (pinfunction "1_1") (pintype "passive"))
      (node (ref "R40") (pin "1") (pinfunction "1_1") (pintype "passive"))
      (node (ref "R41") (pin "1") (pinfunction "1_1") (pintype "passive"))
      (node (ref "R44") (pin "1") (pinfunction "1_1") (pintype "passive"))
      (node (ref "R45") (pin "1") (pinfunction "1_1") (pintype "passive"))
      (node (ref "R46") (pin "1") (pinfunction "1_1") (pintype "passive"))
      (node (ref "R6") (pin "2") (pinfunction "2_2") (pintype "passive"))
      (node (ref "R7") (pin "2") (pinfunction "2_2") (pintype "passive"))
      (node (ref "R8") (pin "1") (pinfunction "1_1") (pintype "passive"))
      (node (ref "SW1") (pin "1@1") (pinfunction "P$1_1@1") (pintype "passive"))
      (node (ref "SW1") (pin "1@2") (pinfunction "P$1_1@2") (pintype "passive"))
      (node (ref "U1") (pin "5") (pinfunction "PGND_5") (pintype "power_in"))
      (node (ref "U1") (pin "8") (pinfunction "AGND_8") (pintype "power_in"))
      (node (ref "U2") (pin "10") (pinfunction "VSS_10") (pintype "power_in"))
      (node (ref "U2") (pin "11") (pinfunction "VSS_11") (pintype "power_in"))
      (node (ref "U2") (pin "PAD") (pinfunction "VSS_PAD") (pintype "power_in"))
      (node (ref "U3") (pin "3") (pinfunction "PGND_3") (pintype "power_in"))
      (node (ref "U3") (pin "9") (pinfunction "GND_9") (pintype "power_in"))
      (node (ref "U3") (pin "PAD") (pinfunction "PGND_PAD") (pintype "power_in"))
      (node (ref "U4") (pin "10") (pinfunction "VSS_10") (pintype "power_in"))
      (node (ref "U4") (pin "11") (pinfunction "VSS_11") (pintype "power_in"))
      (node (ref "U4") (pin "PAD") (pinfunction "VSS_PAD") (pintype "power_in"))
      (node (ref "U5") (pin "8") (pinfunction "VSS_8") (pintype "power_in"))
      (node (ref "U6") (pin "2") (pinfunction "GND_2") (pintype "bidirectional"))
      (node (ref "U7") (pin "1") (pinfunction "GND_1") (pintype "bidirectional"))
      (node (ref "U7") (pin "2") (pinfunction "GND_2") (pintype "bidirectional"))
      (node (ref "U8") (pin "1") (pinfunction "GND_1") (pintype "bidirectional"))
      (node (ref "U8") (pin "2") (pinfunction "GND_2") (pintype "bidirectional"))
      (node (ref "XBT1") (pin "-") (pinfunction "-_-") (pintype "passive"))
      (node (ref "XBT2") (pin "-") (pinfunction "-_-") (pintype "passive"))
    )
    (net (code "3") (name "LOWBAT_TO_PIC") (class "Default")
      (node (ref "D11") (pin "C") (pinfunction "C_C") (pintype "passive"))
      (node (ref "D13") (pin "A") (pinfunction "A_A") (pintype "passive"))
      (node (ref "D14") (pin "A") (pinfunction "A_A") (pintype "passive"))
      (node (ref "R47") (pin "1") (pinfunction "1_1") (pintype "passive"))
      (node (ref "U5") (pin "2") (pinfunction "RA5_2") (pintype "bidirectional"))
    )
    (net (code "4") (name "Net-(C6-Pad2)") (class "Default")
      (node (ref "C6") (pin "2") (pinfunction "2_2") (pintype "passive"))
      (node (ref "C7") (pin "2") (pinfunction "2_2") (pintype "passive"))
      (node (ref "JP1") (pin "1") (pinfunction "1_1") (pintype "passive"))
      (node (ref "L2") (pin "2") (pinfunction "2_2") (pintype "passive"))
      (node (ref "R2") (pin "2") (pinfunction "2_2") (pintype "passive"))
    )
    (net (code "5") (name "Net-(D1-PadA)") (class "Default")
      (node (ref "D1") (pin "A") (pinfunction "A_A") (pintype "passive"))
      (node (ref "R15") (pin "1") (pinfunction "1_1") (pintype "passive"))
      (node (ref "R16") (pin "1") (pinfunction "1_1") (pintype "passive"))
      (node (ref "R17") (pin "1") (pinfunction "1_1") (pintype "passive"))
    )
    (net (code "6") (name "Net-(D2-PadA)") (class "Default")
      (node (ref "D2") (pin "A") (pinfunction "A_A") (pintype "passive"))
      (node (ref "R18") (pin "1") (pinfunction "1_1") (pintype "passive"))
      (node (ref "R49") (pin "1") (pinfunction "1_1") (pintype "passive"))
      (node (ref "R50") (pin "1") (pinfunction "1_1") (pintype "passive"))
    )
    (net (code "7") (name "Net-(D4-C)") (class "Default")
      (node (ref "C1") (pin "+") (pinfunction "+_+") (pintype "passive"))
      (node (ref "C2") (pin "2") (pinfunction "2_2") (pintype "passive"))
      (node (ref "C3") (pin "2") (pinfunction "2_2") (pintype "passive"))
      (node (ref "D4") (pin "K") (pinfunction "C_K") (pintype "passive"))
      (node (ref "R1") (pin "1") (pinfunction "1_1") (pintype "passive"))
      (node (ref "U1") (pin "4") (pinfunction "VIN_4") (pintype "power_in"))
    )
    (net (code "8") (name "Net-(D4-PadA)") (class "Default")
      (node (ref "D4") (pin "A") (pinfunction "A_A") (pintype "passive"))
      (node (ref "J2") (pin "1") (pinfunction "1_1") (pintype "passive"))
    )
    (net (code "9") (name "Net-(D6-PadA)") (class "Default")
      (node (ref "D6") (pin "A") (pinfunction "A_A") (pintype "passive"))
      (node (ref "R35") (pin "1") (pinfunction "1_1") (pintype "passive"))
    )
    (net (code "10") (name "Net-(D8-PadA)") (class "Default")
      (node (ref "D8") (pin "A") (pinfunction "A_A") (pintype "passive"))
      (node (ref "R33") (pin "2") (pinfunction "2_2") (pintype "passive"))
    )
    (net (code "11") (name "Net-(D10-PadA)") (class "Default")
      (node (ref "D10") (pin "A") (pinfunction "A_A") (pintype "passive"))
      (node (ref "R31") (pin "2") (pinfunction "2_2") (pintype "passive"))
    )
    (net (code "12") (name "Net-(D11-PadA)") (class "Default")
      (node (ref "D11") (pin "A") (pinfunction "A_A") (pintype "passive"))
      (node (ref "R32") (pin "2") (pinfunction "2_2") (pintype "passive"))
    )
    (net (code "13") (name "Net-(D15-C)") (class "Default")
      (node (ref "D15") (pin "K") (pinfunction "C_K") (pintype "passive"))
      (node (ref "U7") (pin "4") (pinfunction "~{LBO}_4") (pintype "bidirectional"))
    )
    (net (code "14") (name "Net-(D16-C)") (class "Default")
      (node (ref "D16") (pin "K") (pinfunction "C_K") (pintype "passive"))
      (node (ref "U8") (pin "4") (pinfunction "~{LBO}_4") (pintype "bidirectional"))
    )
    (net (code "15") (name "Net-(J1-D+)") (class "Default")
      (node (ref "J1") (pin "3") (pinfunction "D+_3") (pintype "passive"))
      (node (ref "R19") (pin "1") (pinfunction "1_1") (pintype "passive"))
      (node (ref "R20") (pin "2") (pinfunction "2_2") (pintype "passive"))
      (node (ref "R21") (pin "1") (pinfunction "1_1") (pintype "passive"))
    )
    (net (code "16") (name "Net-(J1-D-)") (class "Default")
      (node (ref "J1") (pin "2") (pinfunction "D-_2") (pintype "passive"))
      (node (ref "R21") (pin "2") (pinfunction "2_2") (pintype "passive"))
      (node (ref "R22") (pin "1") (pinfunction "1_1") (pintype "passive"))
      (node (ref "R23") (pin "2") (pinfunction "2_2") (pintype "passive"))
    )
    (net (code "17") (name "Net-(J1-VCC)") (class "Default")
      (node (ref "C14") (pin "2") (pinfunction "2_2") (pintype "passive"))
      (node (ref "C9") (pin "2") (pinfunction "2_2") (pintype "passive"))
      (node (ref "J1") (pin "1") (pinfunction "VCC_1") (pintype "passive"))
      (node (ref "R19") (pin "2") (pinfunction "2_2") (pintype "passive"))
      (node (ref "R22") (pin "2") (pinfunction "2_2") (pintype "passive"))
      (node (ref "R25") (pin "2") (pinfunction "2_2") (pintype "passive"))
      (node (ref "U3") (pin "1") (pinfunction "VOUT_1") (pintype "output"))
    )
    (net (code "18") (name "Net-(J5-PCLK)") (class "Default")
      (node (ref "J5") (pin "CLK") (pinfunction "PCLK_CLK") (pintype "passive"))
      (node (ref "Q2") (pin "1") (pinfunction "G_1") (pintype "passive"))
      (node (ref "U5") (pin "6") (pinfunction "RA1/PCLK_6") (pintype "bidirectional"))
    )
    (net (code "19") (name "Net-(J5-PDAT)") (class "Default")
      (node (ref "J5") (pin "DAT") (pinfunction "PDAT_DAT") (pintype "passive"))
      (node (ref "Q3") (pin "1") (pinfunction "G_1") (pintype "passive"))
      (node (ref "U5") (pin "7") (pinfunction "RA0/PDAT_7") (pintype "bidirectional"))
    )
    (net (code "20") (name "Net-(J5-~{MCLR})") (class "Default")
      (node (ref "J5") (pin "VPP") (pinfunction "~{MCLR}_VPP") (pintype "passive"))
      (node (ref "R14") (pin "1") (pinfunction "1_1") (pintype "passive"))
      (node (ref "SW1") (pin "2@1") (pinfunction "P$2_2@1") (pintype "passive"))
      (node (ref "SW1") (pin "2@2") (pinfunction "P$2_2@2") (pintype "passive"))
      (node (ref "U5") (pin "4") (pinfunction "~{MCLR}/RA3_4") (pintype "bidirectional"))
    )
    (net (code "21") (name "Net-(Q1-D)") (class "Default")
      (node (ref "Q1") (pin "3") (pinfunction "D_3") (pintype "passive"))
      (node (ref "R15") (pin "2") (pinfunction "2_2") (pintype "passive"))
      (node (ref "R50") (pin "2") (pinfunction "2_2") (pintype "passive"))
    )
    (net (code "22") (name "Net-(Q1-G)") (class "Default")
      (node (ref "Q1") (pin "1") (pinfunction "G_1") (pintype "passive"))
      (node (ref "U5") (pin "5") (pinfunction "RA2_5") (pintype "bidirectional"))
    )
    (net (code "23") (name "Net-(Q2-D)") (class "Default")
      (node (ref "Q2") (pin "3") (pinfunction "D_3") (pintype "passive"))
      (node (ref "R16") (pin "2") (pinfunction "2_2") (pintype "passive"))
      (node (ref "R49") (pin "2") (pinfunction "2_2") (pintype "passive"))
    )
    (net (code "24") (name "Net-(Q3-D)") (class "Default")
      (node (ref "Q3") (pin "3") (pinfunction "D_3") (pintype "passive"))
      (node (ref "R17") (pin "2") (pinfunction "2_2") (pintype "passive"))
      (node (ref "R18") (pin "2") (pinfunction "2_2") (pintype "passive"))
    )
    (net (code "25") (name "Net-(Q4-D)") (class "Default")
      (node (ref "Q4") (pin "3") (pinfunction "D_3") (pintype "passive"))
      (node (ref "R31") (pin "1") (pinfunction "1_1") (pintype "passive"))
    )
    (net (code "26") (name "Net-(Q4-S)") (class "Default")
      (node (ref "Q4") (pin "2") (pinfunction "S_2") (pintype "passive"))
      (node (ref "Q5") (pin "3") (pinfunction "D_3") (pintype "passive"))
      (node (ref "R32") (pin "1") (pinfunction "1_1") (pintype "passive"))
      (node (ref "R34") (pin "1") (pinfunction "1_1") (pintype "passive"))
    )
    (net (code "27") (name "Net-(Q5-G)") (class "Default")
      (node (ref "D12") (pin "A") (pinfunction "A_A") (pintype "passive"))
      (node (ref "D8") (pin "C") (pinfunction "C_C") (pintype "passive"))
      (node (ref "D9") (pin "A") (pinfunction "A_A") (pintype "passive"))
      (node (ref "Q5") (pin "1") (pinfunction "G_1") (pintype "passive"))
      (node (ref "R48") (pin "1") (pinfunction "1_1") (pintype "passive"))
    )
    (net (code "28") (name "Net-(R26-Pad2)") (class "Default")
      (node (ref "R26") (pin "2") (pinfunction "2_2") (pintype "passive"))
      (node (ref "R27") (pin "2") (pinfunction "2_2") (pintype "passive"))
      (node (ref "R45") (pin "2") (pinfunction "2_2") (pintype "passive"))
    )
    (net (code "29") (name "Net-(R28-Pad2)") (class "Default")
      (node (ref "R28") (pin "2") (pinfunction "2_2") (pintype "passive"))
      (node (ref "R29") (pin "2") (pinfunction "2_2") (pintype "passive"))
      (node (ref "R46") (pin "2") (pinfunction "2_2") (pintype "passive"))
    )
    (net (code "30") (name "Net-(R36-Pad1)") (class "Default")
      (node (ref "R36") (pin "1") (pinfunction "1_1") (pintype "passive"))
      (node (ref "R37") (pin "2") (pinfunction "2_2") (pintype "passive"))
    )
    (net (code "31") (name "Net-(R38-Pad1)") (class "Default")
      (node (ref "R38") (pin "1") (pinfunction "1_1") (pintype "passive"))
      (node (ref "R39") (pin "2") (pinfunction "2_2") (pintype "passive"))
    )
    (net (code "32") (name "Net-(U1-BOOST)") (class "Default")
      (node (ref "C5") (pin "2") (pinfunction "2_2") (pintype "passive"))
      (node (ref "U1") (pin "7") (pinfunction "BOOST_7") (pintype "output"))
    )
    (net (code "33") (name "Net-(U1-EN)") (class "Default")
      (node (ref "R1") (pin "2") (pinfunction "2_2") (pintype "passive"))
      (node (ref "U1") (pin "3") (pinfunction "EN_3") (pintype "input"))
    )
    (net (code "34") (name "Net-(U1-SW)") (class "Default")
      (node (ref "C5") (pin "1") (pinfunction "1_1") (pintype "passive"))
      (node (ref "L2") (pin "1") (pinfunction "1_1") (pintype "passive"))
      (node (ref "U1") (pin "6") (pinfunction "SW_6") (pintype "output"))
    )
    (net (code "35") (name "Net-(U1-VCC)") (class "Default")
      (node (ref "C4") (pin "2") (pinfunction "2_2") (pintype "passive"))
      (node (ref "U1") (pin "2") (pinfunction "VCC_2") (pintype "output"))
    )
    (net (code "36") (name "Net-(U1-VFB)") (class "Default")
      (node (ref "R2") (pin "1") (pinfunction "1_1") (pintype "passive"))
      (node (ref "R3") (pin "2") (pinfunction "2_2") (pintype "passive"))
      (node (ref "U1") (pin "1") (pinfunction "VFB_1") (pintype "input"))
    )
    (net (code "37") (name "Net-(U2-PROG1)") (class "Default")
      (node (ref "R6") (pin "1") (pinfunction "1_1") (pintype "passive"))
      (node (ref "U2") (pin "13") (pinfunction "PROG1_13") (pintype "input"))
    )
    (net (code "38") (name "Net-(U2-PROG3)") (class "Default")
      (node (ref "R7") (pin "1") (pinfunction "1_1") (pintype "passive"))
      (node (ref "U2") (pin "12") (pinfunction "PROG3_12") (pintype "input"))
    )
    (net (code "39") (name "Net-(U2-THERM)") (class "Default")
      (node (ref "R26") (pin "1") (pinfunction "1_1") (pintype "passive"))
      (node (ref "R27") (pin "1") (pinfunction "1_1") (pintype "passive"))
      (node (ref "U2") (pin "5") (pinfunction "THERM_5") (pintype "input"))
    )
    (net (code "40") (name "Net-(U2-VBAT_SENSE)") (class "Default")
      (node (ref "C16") (pin "2") (pinfunction "2_2") (pintype "passive"))
      (node (ref "U2") (pin "14") (pinfunction "VBAT_14") (pintype "power_in"))
      (node (ref "U2") (pin "15") (pinfunction "VBAT_15") (pintype "power_in"))
      (node (ref "U2") (pin "16") (pinfunction "VBAT_SENSE_16") (pintype "input"))
      (node (ref "XBT1") (pin "+") (pinfunction "+_+") (pintype "passive"))
    )
    (net (code "41") (name "Net-(U2-VPCC)") (class "Default")
      (node (ref "R4") (pin "2") (pinfunction "2_2") (pintype "passive"))
      (node (ref "R5") (pin "1") (pinfunction "1_1") (pintype "passive"))
      (node (ref "U2") (pin "2") (pinfunction "VPCC_2") (pintype "input"))
    )
    (net (code "42") (name "Net-(U3-FB)") (class "Default")
      (node (ref "R24") (pin "2") (pinfunction "2_2") (pintype "passive"))
      (node (ref "R25") (pin "1") (pinfunction "1_1") (pintype "passive"))
      (node (ref "U3") (pin "10") (pinfunction "FB_10") (pintype "input"))
    )
    (net (code "43") (name "Net-(U3-L1)") (class "Default")
      (node (ref "L3") (pin "1") (pinfunction "1_1") (pintype "passive"))
      (node (ref "U3") (pin "4") (pinfunction "L1_4") (pintype "input"))
    )
    (net (code "44") (name "Net-(U3-L2)") (class "Default")
      (node (ref "L3") (pin "2") (pinfunction "2_2") (pintype "passive"))
      (node (ref "U3") (pin "2") (pinfunction "L2_2") (pintype "input"))
    )
    (net (code "45") (name "Net-(U3-PS{slash}SYNC)") (class "Default")
      (node (ref "R43") (pin "1") (pinfunction "1_1") (pintype "passive"))
      (node (ref "R44") (pin "2") (pinfunction "2_2") (pintype "passive"))
      (node (ref "U3") (pin "7") (pinfunction "PS/SYNC_7") (pintype "input"))
    )
    (net (code "46") (name "Net-(U3-VIN)") (class "Default")
      (node (ref "C8") (pin "2") (pinfunction "2_2") (pintype "passive"))
      (node (ref "JP2") (pin "2") (pinfunction "2_2") (pintype "passive"))
      (node (ref "U3") (pin "5") (pinfunction "VIN_5") (pintype "power_in"))
    )
    (net (code "47") (name "Net-(U3-VINA)") (class "Default")
      (node (ref "C15") (pin "2") (pinfunction "2_2") (pintype "passive"))
      (node (ref "R43") (pin "2") (pinfunction "2_2") (pintype "passive"))
      (node (ref "U3") (pin "8") (pinfunction "VINA_8") (pintype "passive"))
    )
    (net (code "48") (name "Net-(U4-CE)") (class "Default")
      (node (ref "D7") (pin "A") (pinfunction "A_A") (pintype "passive"))
      (node (ref "R30") (pin "1") (pinfunction "1_1") (pintype "passive"))
      (node (ref "U4") (pin "17") (pinfunction "CE_17") (pintype "input"))
    )
    (net (code "49") (name "Net-(U4-PROG1)") (class "Default")
      (node (ref "R10") (pin "1") (pinfunction "1_1") (pintype "passive"))
      (node (ref "U4") (pin "13") (pinfunction "PROG1_13") (pintype "input"))
    )
    (net (code "50") (name "Net-(U4-PROG3)") (class "Default")
      (node (ref "R11") (pin "1") (pinfunction "1_1") (pintype "passive"))
      (node (ref "U4") (pin "12") (pinfunction "PROG3_12") (pintype "input"))
    )
    (net (code "51") (name "Net-(U4-THERM)") (class "Default")
      (node (ref "R28") (pin "1") (pinfunction "1_1") (pintype "passive"))
      (node (ref "R29") (pin "1") (pinfunction "1_1") (pintype "passive"))
      (node (ref "U4") (pin "5") (pinfunction "THERM_5") (pintype "input"))
    )
    (net (code "52") (name "Net-(U4-VBAT_SENSE)") (class "Default")
      (node (ref "C17") (pin "2") (pinfunction "2_2") (pintype "passive"))
      (node (ref "U4") (pin "14") (pinfunction "VBAT_14") (pintype "power_in"))
      (node (ref "U4") (pin "15") (pinfunction "VBAT_15") (pintype "power_in"))
      (node (ref "U4") (pin "16") (pinfunction "VBAT_SENSE_16") (pintype "input"))
      (node (ref "XBT2") (pin "+") (pinfunction "+_+") (pintype "passive"))
    )
    (net (code "53") (name "Net-(U4-VPCC)") (class "Default")
      (node (ref "R8") (pin "2") (pinfunction "2_2") (pintype "passive"))
      (node (ref "R9") (pin "1") (pinfunction "1_1") (pintype "passive"))
      (node (ref "U4") (pin "2") (pinfunction "VPCC_2") (pintype "input"))
    )
    (net (code "54") (name "Net-(U5-RA4)") (class "Default")
      (node (ref "R35") (pin "2") (pinfunction "2_2") (pintype "passive"))
      (node (ref "U5") (pin "3") (pinfunction "RA4_3") (pintype "bidirectional"))
    )
    (net (code "55") (name "Net-(U6-ADJ)") (class "Default")
      (node (ref "R12") (pin "2") (pinfunction "2_2") (pintype "passive"))
      (node (ref "R13") (pin "1") (pinfunction "1_1") (pintype "passive"))
      (node (ref "U6") (pin "4") (pinfunction "ADJ_4") (pintype "bidirectional"))
    )
    (net (code "56") (name "Net-(U6-VIN)") (class "Default")
      (node (ref "JP3") (pin "2") (pinfunction "2_2") (pintype "passive"))
      (node (ref "U6") (pin "1") (pinfunction "VIN_1") (pintype "bidirectional"))
    )
    (net (code "57") (name "Net-(U7-BAT)") (class "Default")
      (node (ref "C10") (pin "2") (pinfunction "2_2") (pintype "passive"))
      (node (ref "D3") (pin "A") (pinfunction "A_A") (pintype "passive"))
      (node (ref "R36") (pin "2") (pinfunction "2_2") (pintype "passive"))
      (node (ref "U2") (pin "1") (pinfunction "OUT_1") (pintype "power_in"))
      (node (ref "U2") (pin "20") (pinfunction "OUT_20") (pintype "power_in"))
      (node (ref "U7") (pin "5") (pinfunction "BAT_5") (pintype "bidirectional"))
    )
    (net (code "58") (name "Net-(U7-LBI)") (class "Default")
      (node (ref "R37") (pin "1") (pinfunction "1_1") (pintype "passive"))
      (node (ref "R40") (pin "2") (pinfunction "2_2") (pintype "passive"))
      (node (ref "U7") (pin "3") (pinfunction "LBI_3") (pintype "bidirectional"))
    )
    (net (code "59") (name "Net-(U8-BAT)") (class "Default")
      (node (ref "C11") (pin "2") (pinfunction "2_2") (pintype "passive"))
      (node (ref "D5") (pin "A") (pinfunction "A_A") (pintype "passive"))
      (node (ref "R38") (pin "2") (pinfunction "2_2") (pintype "passive"))
      (node (ref "U4") (pin "1") (pinfunction "OUT_1") (pintype "power_in"))
      (node (ref "U4") (pin "20") (pinfunction "OUT_20") (pintype "power_in"))
      (node (ref "U8") (pin "5") (pinfunction "BAT_5") (pintype "bidirectional"))
    )
    (net (code "60") (name "Net-(U8-LBI)") (class "Default")
      (node (ref "R39") (pin "1") (pinfunction "1_1") (pintype "passive"))
      (node (ref "R41") (pin "2") (pinfunction "2_2") (pintype "passive"))
      (node (ref "U8") (pin "3") (pinfunction "LBI_3") (pintype "bidirectional"))
    )
    (net (code "61") (name "SOLAR_5VMAX") (class "Default")
      (node (ref "JP1") (pin "2") (pinfunction "2_2") (pintype "passive"))
      (node (ref "Q5") (pin "2") (pinfunction "S_2") (pintype "passive"))
      (node (ref "R30") (pin "2") (pinfunction "2_2") (pintype "passive"))
      (node (ref "R33") (pin "1") (pinfunction "1_1") (pintype "passive"))
      (node (ref "R48") (pin "2") (pinfunction "2_2") (pintype "passive"))
      (node (ref "R5") (pin "2") (pinfunction "2_2") (pintype "passive"))
      (node (ref "R9") (pin "2") (pinfunction "2_2") (pintype "passive"))
      (node (ref "U2") (pin "17") (pinfunction "CE_17") (pintype "input"))
      (node (ref "U2") (pin "18") (pinfunction "IN_18") (pintype "power_in"))
      (node (ref "U2") (pin "19") (pinfunction "IN_19") (pintype "power_in"))
      (node (ref "U2") (pin "3") (pinfunction "SEL_3") (pintype "input"))
      (node (ref "U2") (pin "4") (pinfunction "PROG2_4") (pintype "input"))
      (node (ref "U2") (pin "9") (pinfunction "~{TE}_9") (pintype "input"))
      (node (ref "U4") (pin "18") (pinfunction "IN_18") (pintype "power_in"))
      (node (ref "U4") (pin "19") (pinfunction "IN_19") (pintype "power_in"))
      (node (ref "U4") (pin "3") (pinfunction "SEL_3") (pintype "input"))
      (node (ref "U4") (pin "4") (pinfunction "PROG2_4") (pintype "input"))
      (node (ref "U4") (pin "9") (pinfunction "~{TE}_9") (pintype "input"))
    )
    (net (code "62") (name "STAT1A") (class "Default")
      (node (ref "D14") (pin "K") (pinfunction "C_K") (pintype "passive"))
      (node (ref "D7") (pin "K") (pinfunction "C_K") (pintype "passive"))
      (node (ref "U2") (pin "8") (pinfunction "STAT1/~{LBO}_8") (pintype "output"))
    )
    (net (code "63") (name "STAT1B") (class "Default")
      (node (ref "D13") (pin "K") (pinfunction "C_K") (pintype "passive"))
      (node (ref "U4") (pin "8") (pinfunction "STAT1/~{LBO}_8") (pintype "output"))
    )
    (net (code "64") (name "STAT2A") (class "Default")
      (node (ref "D10") (pin "C") (pinfunction "C_C") (pintype "passive"))
      (node (ref "U2") (pin "7") (pinfunction "STAT2_7") (pintype "output"))
    )
    (net (code "65") (name "STAT2B") (class "Default")
      (node (ref "Q4") (pin "1") (pinfunction "G_1") (pintype "passive"))
      (node (ref "R34") (pin "2") (pinfunction "2_2") (pintype "passive"))
      (node (ref "U4") (pin "7") (pinfunction "STAT2_7") (pintype "output"))
    )
    (net (code "66") (name "SYSTEM_POWER") (class "Default")
      (node (ref "D3") (pin "K") (pinfunction "C_K") (pintype "passive"))
      (node (ref "D5") (pin "K") (pinfunction "C_K") (pintype "passive"))
      (node (ref "JP2") (pin "1") (pinfunction "1_1") (pintype "passive"))
      (node (ref "JP3") (pin "1") (pinfunction "1_1") (pintype "passive"))
      (node (ref "R42") (pin "2") (pinfunction "2_2") (pintype "passive"))
    )
    (net (code "67") (name "~{BAT_LOW}") (class "Default")
      (node (ref "D15") (pin "A") (pinfunction "A_A") (pintype "passive"))
      (node (ref "D16") (pin "A") (pinfunction "A_A") (pintype "passive"))
      (node (ref "R42") (pin "1") (pinfunction "1_1") (pintype "passive"))
      (node (ref "U3") (pin "6") (pinfunction "EN_6") (pintype "input"))
      (node (ref "U6") (pin "3") (pinfunction "~{SHDN}_3") (pintype "bidirectional"))
    )
    (net (code "68") (name "~{PGA}") (class "Default")
      (node (ref "D12") (pin "K") (pinfunction "C_K") (pintype "passive"))
      (node (ref "U2") (pin "6") (pinfunction "~{PG}_6") (pintype "output"))
    )
    (net (code "69") (name "~{PGB}") (class "Default")
      (node (ref "D9") (pin "K") (pinfunction "C_K") (pintype "passive"))
      (node (ref "U4") (pin "6") (pinfunction "~{PG}_6") (pintype "output"))
    )
  )
)
